# top.net
KiCad netlist of a schematic drawn in Altium Designer
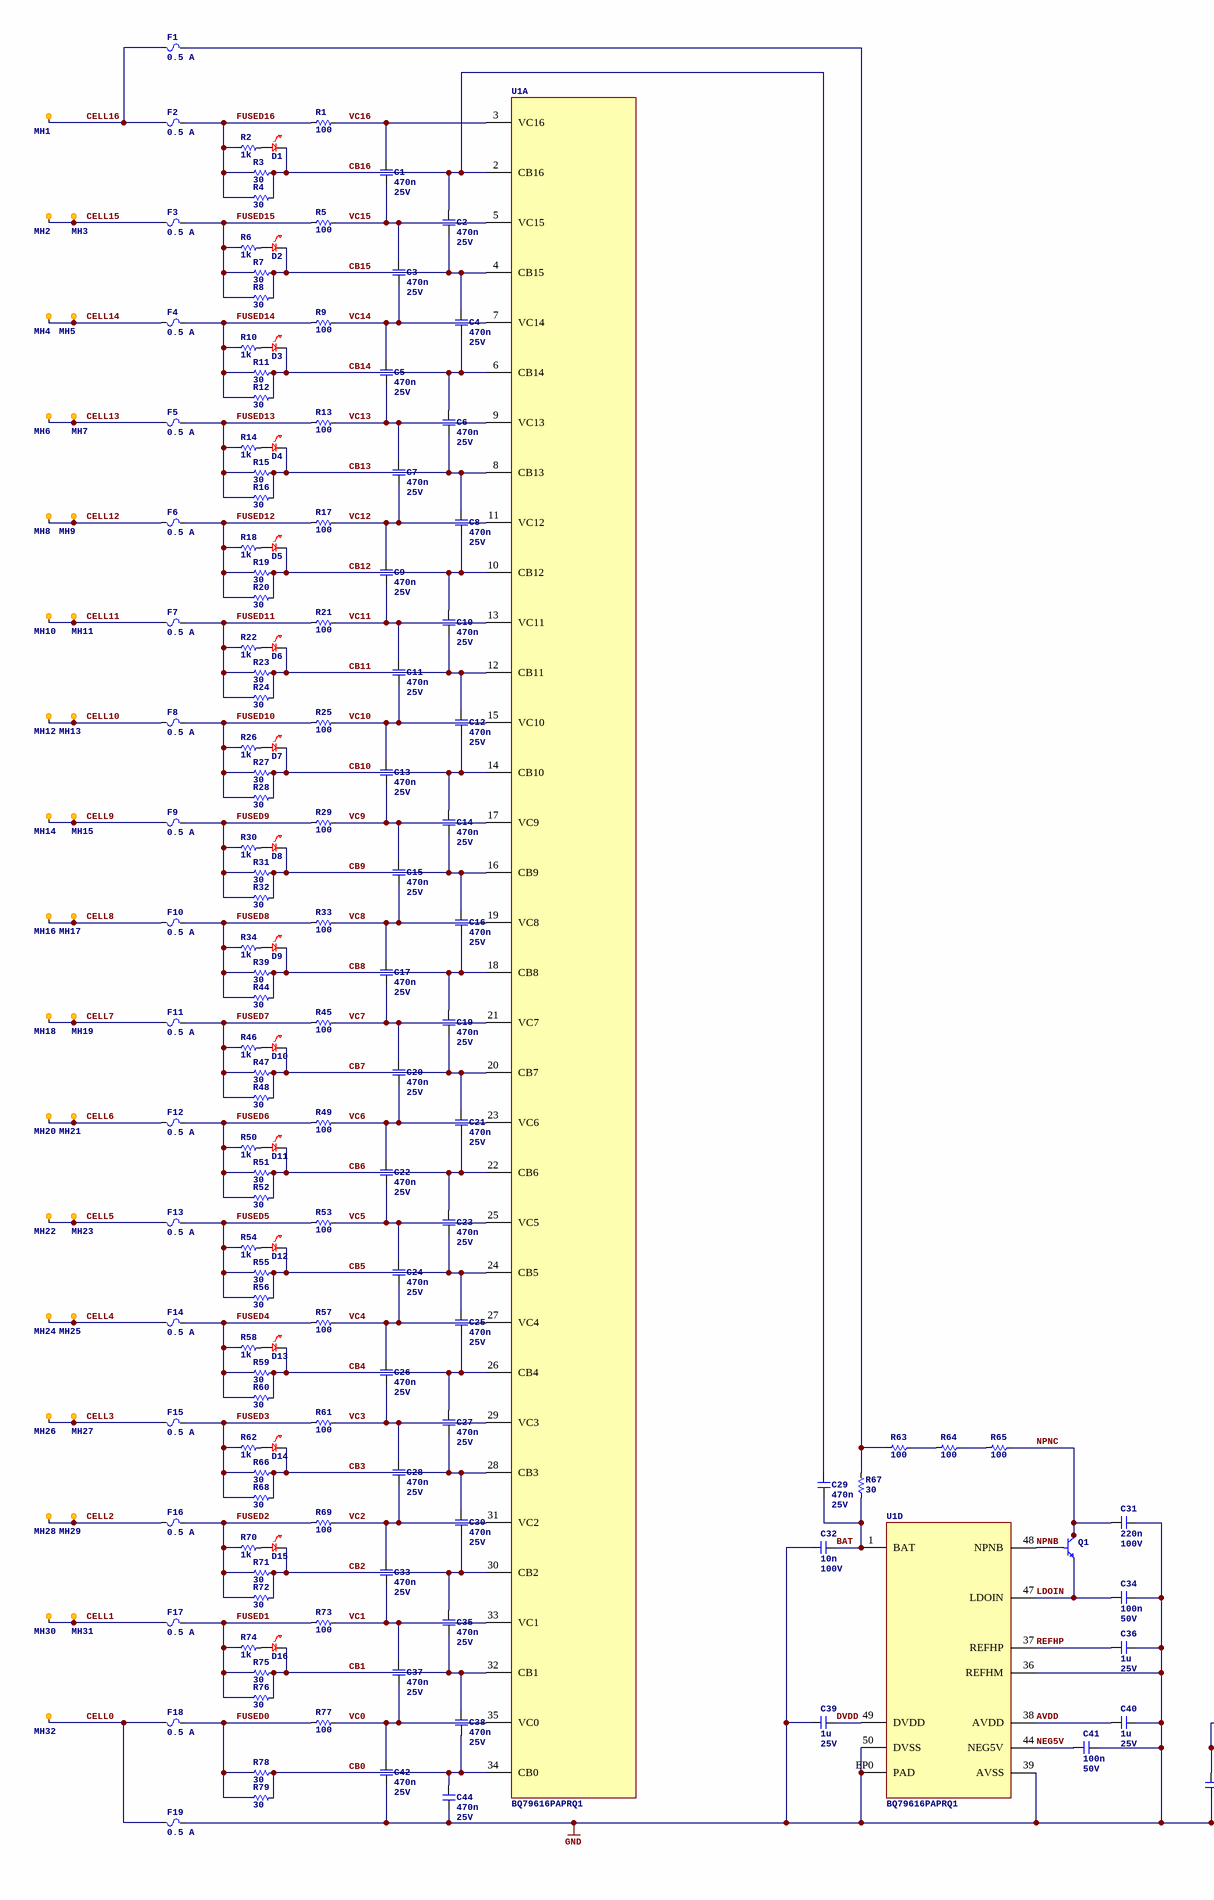
[diagram p0: top.SchDoc, left]
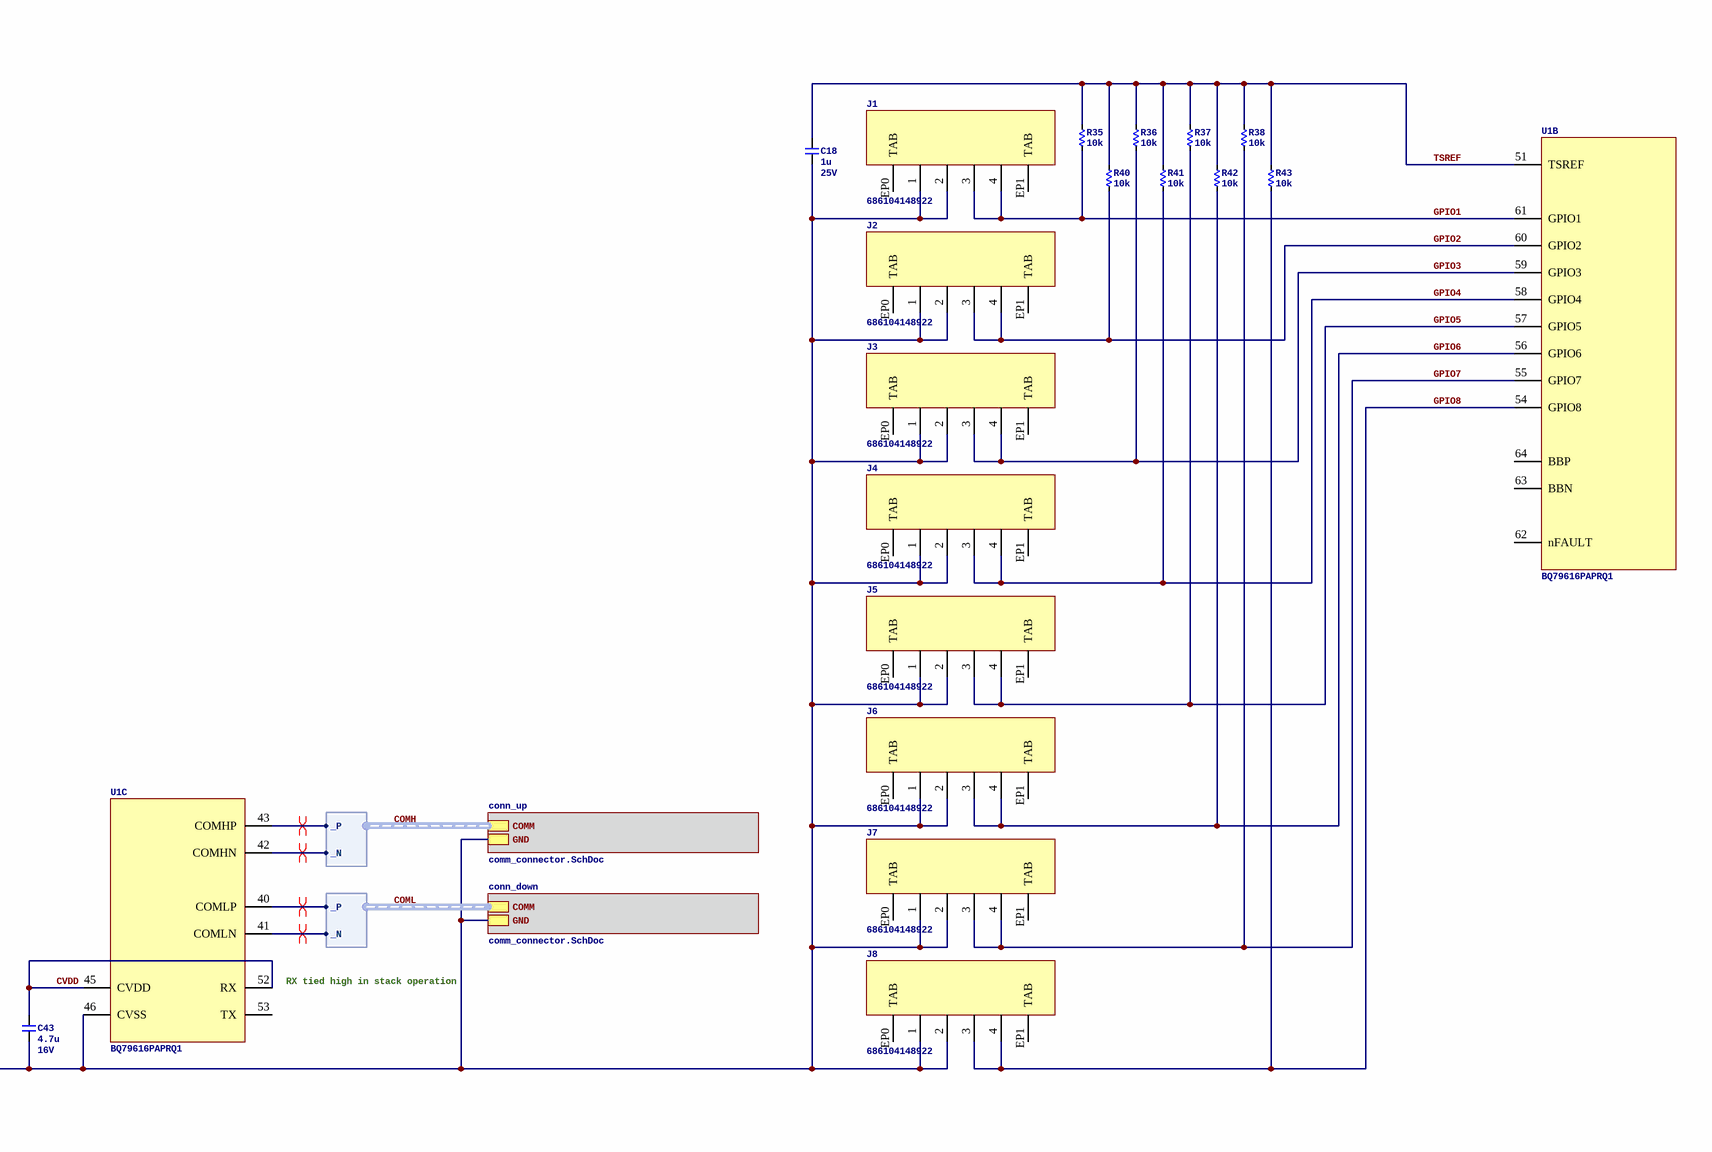
[diagram p1: top.SchDoc, right]

(export (version "E")
  (design (tool "Eeschema 10.0.6"))
  (components
    (comp (ref "C1")
      (value "CL10B474KA8NNNC")
      (footprint "C0603")
      (fields
        (field (name "CAPACITANCE") "470n")
        (field (name "MANUFACTURER") "Samsung Electro-Mechanics")
        (field (name "VOLTAGE RATING") "25V")
      )
      (libsource (lib "database") (part "__template_cap"))
    )
    (comp (ref "C2")
      (value "CL10B474KA8NNNC")
      (footprint "C0603")
      (fields
        (field (name "CAPACITANCE") "470n")
        (field (name "MANUFACTURER") "Samsung Electro-Mechanics")
        (field (name "VOLTAGE RATING") "25V")
      )
      (libsource (lib "database") (part "__template_cap"))
    )
    (comp (ref "C3")
      (value "CL10B474KA8NNNC")
      (footprint "C0603")
      (fields
        (field (name "CAPACITANCE") "470n")
        (field (name "MANUFACTURER") "Samsung Electro-Mechanics")
        (field (name "VOLTAGE RATING") "25V")
      )
      (libsource (lib "database") (part "__template_cap"))
    )
    (comp (ref "C4")
      (value "CL10B474KA8NNNC")
      (footprint "C0603")
      (fields
        (field (name "CAPACITANCE") "470n")
        (field (name "MANUFACTURER") "Samsung Electro-Mechanics")
        (field (name "VOLTAGE RATING") "25V")
      )
      (libsource (lib "database") (part "__template_cap"))
    )
    (comp (ref "C5")
      (value "CL10B474KA8NNNC")
      (footprint "C0603")
      (fields
        (field (name "CAPACITANCE") "470n")
        (field (name "MANUFACTURER") "Samsung Electro-Mechanics")
        (field (name "VOLTAGE RATING") "25V")
      )
      (libsource (lib "database") (part "__template_cap"))
    )
    (comp (ref "C6")
      (value "CL10B474KA8NNNC")
      (footprint "C0603")
      (fields
        (field (name "CAPACITANCE") "470n")
        (field (name "MANUFACTURER") "Samsung Electro-Mechanics")
        (field (name "VOLTAGE RATING") "25V")
      )
      (libsource (lib "database") (part "__template_cap"))
    )
    (comp (ref "C7")
      (value "CL10B474KA8NNNC")
      (footprint "C0603")
      (fields
        (field (name "CAPACITANCE") "470n")
        (field (name "MANUFACTURER") "Samsung Electro-Mechanics")
        (field (name "VOLTAGE RATING") "25V")
      )
      (libsource (lib "database") (part "__template_cap"))
    )
    (comp (ref "C8")
      (value "CL10B474KA8NNNC")
      (footprint "C0603")
      (fields
        (field (name "CAPACITANCE") "470n")
        (field (name "MANUFACTURER") "Samsung Electro-Mechanics")
        (field (name "VOLTAGE RATING") "25V")
      )
      (libsource (lib "database") (part "__template_cap"))
    )
    (comp (ref "C9")
      (value "CL10B474KA8NNNC")
      (footprint "C0603")
      (fields
        (field (name "CAPACITANCE") "470n")
        (field (name "MANUFACTURER") "Samsung Electro-Mechanics")
        (field (name "VOLTAGE RATING") "25V")
      )
      (libsource (lib "database") (part "__template_cap"))
    )
    (comp (ref "C10")
      (value "CL10B474KA8NNNC")
      (footprint "C0603")
      (fields
        (field (name "CAPACITANCE") "470n")
        (field (name "MANUFACTURER") "Samsung Electro-Mechanics")
        (field (name "VOLTAGE RATING") "25V")
      )
      (libsource (lib "database") (part "__template_cap"))
    )
    (comp (ref "C11")
      (value "CL10B474KA8NNNC")
      (footprint "C0603")
      (fields
        (field (name "CAPACITANCE") "470n")
        (field (name "MANUFACTURER") "Samsung Electro-Mechanics")
        (field (name "VOLTAGE RATING") "25V")
      )
      (libsource (lib "database") (part "__template_cap"))
    )
    (comp (ref "C12")
      (value "CL10B474KA8NNNC")
      (footprint "C0603")
      (fields
        (field (name "CAPACITANCE") "470n")
        (field (name "MANUFACTURER") "Samsung Electro-Mechanics")
        (field (name "VOLTAGE RATING") "25V")
      )
      (libsource (lib "database") (part "__template_cap"))
    )
    (comp (ref "C13")
      (value "CL10B474KA8NNNC")
      (footprint "C0603")
      (fields
        (field (name "CAPACITANCE") "470n")
        (field (name "MANUFACTURER") "Samsung Electro-Mechanics")
        (field (name "VOLTAGE RATING") "25V")
      )
      (libsource (lib "database") (part "__template_cap"))
    )
    (comp (ref "C14")
      (value "CL10B474KA8NNNC")
      (footprint "C0603")
      (fields
        (field (name "CAPACITANCE") "470n")
        (field (name "MANUFACTURER") "Samsung Electro-Mechanics")
        (field (name "VOLTAGE RATING") "25V")
      )
      (libsource (lib "database") (part "__template_cap"))
    )
    (comp (ref "C15")
      (value "CL10B474KA8NNNC")
      (footprint "C0603")
      (fields
        (field (name "CAPACITANCE") "470n")
        (field (name "MANUFACTURER") "Samsung Electro-Mechanics")
        (field (name "VOLTAGE RATING") "25V")
      )
      (libsource (lib "database") (part "__template_cap"))
    )
    (comp (ref "C16")
      (value "CL10B474KA8NNNC")
      (footprint "C0603")
      (fields
        (field (name "CAPACITANCE") "470n")
        (field (name "MANUFACTURER") "Samsung Electro-Mechanics")
        (field (name "VOLTAGE RATING") "25V")
      )
      (libsource (lib "database") (part "__template_cap"))
    )
    (comp (ref "C17")
      (value "CL10B474KA8NNNC")
      (footprint "C0603")
      (fields
        (field (name "CAPACITANCE") "470n")
        (field (name "MANUFACTURER") "Samsung Electro-Mechanics")
        (field (name "VOLTAGE RATING") "25V")
      )
      (libsource (lib "database") (part "__template_cap"))
    )
    (comp (ref "C18")
      (value "CL10B105KA8NNNC")
      (footprint "C0603")
      (fields
        (field (name "CAPACITANCE") "1u")
        (field (name "MANUFACTURER") "Samsung Electro-Mechanics")
        (field (name "VOLTAGE RATING") "25V")
      )
      (libsource (lib "database") (part "__template_cap"))
    )
    (comp (ref "C19")
      (value "CL10B474KA8NNNC")
      (footprint "C0603")
      (fields
        (field (name "CAPACITANCE") "470n")
        (field (name "MANUFACTURER") "Samsung Electro-Mechanics")
        (field (name "VOLTAGE RATING") "25V")
      )
      (libsource (lib "database") (part "__template_cap"))
    )
    (comp (ref "C20")
      (value "CL10B474KA8NNNC")
      (footprint "C0603")
      (fields
        (field (name "CAPACITANCE") "470n")
        (field (name "MANUFACTURER") "Samsung Electro-Mechanics")
        (field (name "VOLTAGE RATING") "25V")
      )
      (libsource (lib "database") (part "__template_cap"))
    )
    (comp (ref "C21")
      (value "CL10B474KA8NNNC")
      (footprint "C0603")
      (fields
        (field (name "CAPACITANCE") "470n")
        (field (name "MANUFACTURER") "Samsung Electro-Mechanics")
        (field (name "VOLTAGE RATING") "25V")
      )
      (libsource (lib "database") (part "__template_cap"))
    )
    (comp (ref "C22")
      (value "CL10B474KA8NNNC")
      (footprint "C0603")
      (fields
        (field (name "CAPACITANCE") "470n")
        (field (name "MANUFACTURER") "Samsung Electro-Mechanics")
        (field (name "VOLTAGE RATING") "25V")
      )
      (libsource (lib "database") (part "__template_cap"))
    )
    (comp (ref "C23")
      (value "CL10B474KA8NNNC")
      (footprint "C0603")
      (fields
        (field (name "CAPACITANCE") "470n")
        (field (name "MANUFACTURER") "Samsung Electro-Mechanics")
        (field (name "VOLTAGE RATING") "25V")
      )
      (libsource (lib "database") (part "__template_cap"))
    )
    (comp (ref "C24")
      (value "CL10B474KA8NNNC")
      (footprint "C0603")
      (fields
        (field (name "CAPACITANCE") "470n")
        (field (name "MANUFACTURER") "Samsung Electro-Mechanics")
        (field (name "VOLTAGE RATING") "25V")
      )
      (libsource (lib "database") (part "__template_cap"))
    )
    (comp (ref "C25")
      (value "CL10B474KA8NNNC")
      (footprint "C0603")
      (fields
        (field (name "CAPACITANCE") "470n")
        (field (name "MANUFACTURER") "Samsung Electro-Mechanics")
        (field (name "VOLTAGE RATING") "25V")
      )
      (libsource (lib "database") (part "__template_cap"))
    )
    (comp (ref "C26")
      (value "CL10B474KA8NNNC")
      (footprint "C0603")
      (fields
        (field (name "CAPACITANCE") "470n")
        (field (name "MANUFACTURER") "Samsung Electro-Mechanics")
        (field (name "VOLTAGE RATING") "25V")
      )
      (libsource (lib "database") (part "__template_cap"))
    )
    (comp (ref "C27")
      (value "CL10B474KA8NNNC")
      (footprint "C0603")
      (fields
        (field (name "CAPACITANCE") "470n")
        (field (name "MANUFACTURER") "Samsung Electro-Mechanics")
        (field (name "VOLTAGE RATING") "25V")
      )
      (libsource (lib "database") (part "__template_cap"))
    )
    (comp (ref "C28")
      (value "CL10B474KA8NNNC")
      (footprint "C0603")
      (fields
        (field (name "CAPACITANCE") "470n")
        (field (name "MANUFACTURER") "Samsung Electro-Mechanics")
        (field (name "VOLTAGE RATING") "25V")
      )
      (libsource (lib "database") (part "__template_cap"))
    )
    (comp (ref "C29")
      (value "CL10B474KA8NNNC")
      (footprint "C0603")
      (fields
        (field (name "CAPACITANCE") "470n")
        (field (name "MANUFACTURER") "Samsung Electro-Mechanics")
        (field (name "VOLTAGE RATING") "25V")
      )
      (libsource (lib "database") (part "__template_cap"))
    )
    (comp (ref "C30")
      (value "CL10B474KA8NNNC")
      (footprint "C0603")
      (fields
        (field (name "CAPACITANCE") "470n")
        (field (name "MANUFACTURER") "Samsung Electro-Mechanics")
        (field (name "VOLTAGE RATING") "25V")
      )
      (libsource (lib "database") (part "__template_cap"))
    )
    (comp (ref "C31")
      (value "TCC1206X7R224K101FT")
      (footprint "C1206")
      (fields
        (field (name "CAPACITANCE") "220n")
        (field (name "MANUFACTURER") "CCTC")
        (field (name "VOLTAGE RATING") "100V")
      )
      (libsource (lib "database") (part "__template_cap"))
    )
    (comp (ref "C32")
      (value "CC0402KRX7R0BB103")
      (footprint "C0402")
      (fields
        (field (name "CAPACITANCE") "10n")
        (field (name "MANUFACTURER") "YAGEO")
        (field (name "VOLTAGE RATING") "100V")
      )
      (libsource (lib "database") (part "__template_cap"))
    )
    (comp (ref "C33")
      (value "CL10B474KA8NNNC")
      (footprint "C0603")
      (fields
        (field (name "CAPACITANCE") "470n")
        (field (name "MANUFACTURER") "Samsung Electro-Mechanics")
        (field (name "VOLTAGE RATING") "25V")
      )
      (libsource (lib "database") (part "__template_cap"))
    )
    (comp (ref "C34")
      (value "CL05B104KB54PNC")
      (footprint "C0402")
      (fields
        (field (name "CAPACITANCE") "100n")
        (field (name "MANUFACTURER") "Samsung Electro-Mechanics")
        (field (name "VOLTAGE RATING") "50V")
      )
      (libsource (lib "database") (part "__template_cap"))
    )
    (comp (ref "C35")
      (value "CL10B474KA8NNNC")
      (footprint "C0603")
      (fields
        (field (name "CAPACITANCE") "470n")
        (field (name "MANUFACTURER") "Samsung Electro-Mechanics")
        (field (name "VOLTAGE RATING") "25V")
      )
      (libsource (lib "database") (part "__template_cap"))
    )
    (comp (ref "C36")
      (value "CL10B105KA8NNNC")
      (footprint "C0603")
      (fields
        (field (name "CAPACITANCE") "1u")
        (field (name "MANUFACTURER") "Samsung Electro-Mechanics")
        (field (name "VOLTAGE RATING") "25V")
      )
      (libsource (lib "database") (part "__template_cap"))
    )
    (comp (ref "C37")
      (value "CL10B474KA8NNNC")
      (footprint "C0603")
      (fields
        (field (name "CAPACITANCE") "470n")
        (field (name "MANUFACTURER") "Samsung Electro-Mechanics")
        (field (name "VOLTAGE RATING") "25V")
      )
      (libsource (lib "database") (part "__template_cap"))
    )
    (comp (ref "C38")
      (value "CL10B474KA8NNNC")
      (footprint "C0603")
      (fields
        (field (name "CAPACITANCE") "470n")
        (field (name "MANUFACTURER") "Samsung Electro-Mechanics")
        (field (name "VOLTAGE RATING") "25V")
      )
      (libsource (lib "database") (part "__template_cap"))
    )
    (comp (ref "C39")
      (value "CL10B105KA8NNNC")
      (footprint "C0603")
      (fields
        (field (name "CAPACITANCE") "1u")
        (field (name "MANUFACTURER") "Samsung Electro-Mechanics")
        (field (name "VOLTAGE RATING") "25V")
      )
      (libsource (lib "database") (part "__template_cap"))
    )
    (comp (ref "C40")
      (value "CL10B105KA8NNNC")
      (footprint "C0603")
      (fields
        (field (name "CAPACITANCE") "1u")
        (field (name "MANUFACTURER") "Samsung Electro-Mechanics")
        (field (name "VOLTAGE RATING") "25V")
      )
      (libsource (lib "database") (part "__template_cap"))
    )
    (comp (ref "C41")
      (value "CL05B104KB54PNC")
      (footprint "C0402")
      (fields
        (field (name "CAPACITANCE") "100n")
        (field (name "MANUFACTURER") "Samsung Electro-Mechanics")
        (field (name "VOLTAGE RATING") "50V")
      )
      (libsource (lib "database") (part "__template_cap"))
    )
    (comp (ref "C42")
      (value "CL10B474KA8NNNC")
      (footprint "C0603")
      (fields
        (field (name "CAPACITANCE") "470n")
        (field (name "MANUFACTURER") "Samsung Electro-Mechanics")
        (field (name "VOLTAGE RATING") "25V")
      )
      (libsource (lib "database") (part "__template_cap"))
    )
    (comp (ref "C43")
      (value "CL21B475KOFNNNE")
      (footprint "C0805")
      (fields
        (field (name "CAPACITANCE") "4.7u")
        (field (name "MANUFACTURER") "Samsung Electro-Mechanics")
        (field (name "VOLTAGE RATING") "16V")
      )
      (libsource (lib "database") (part "__template_cap"))
    )
    (comp (ref "C44")
      (value "CL10B474KA8NNNC")
      (footprint "C0603")
      (fields
        (field (name "CAPACITANCE") "470n")
        (field (name "MANUFACTURER") "Samsung Electro-Mechanics")
        (field (name "VOLTAGE RATING") "25V")
      )
      (libsource (lib "database") (part "__template_cap"))
    )
    (comp (ref "D1")
      (value "LTST-C190KRKT")
      (footprint "LED_0603P_RED")
      (description "LED SUPER RED CLEAR 0603 SMD")
      (fields (field (name "MANUFACTURER") "Lite-On Inc"))
      (libsource (lib "SSCP") (part "LED_0603_RED_LTST-C190KRKT"))
    )
    (comp (ref "D2")
      (value "LTST-C190KRKT")
      (footprint "LED_0603P_RED")
      (description "LED SUPER RED CLEAR 0603 SMD")
      (fields (field (name "MANUFACTURER") "Lite-On Inc"))
      (libsource (lib "SSCP") (part "LED_0603_RED_LTST-C190KRKT"))
    )
    (comp (ref "D3")
      (value "LTST-C190KRKT")
      (footprint "LED_0603P_RED")
      (description "LED SUPER RED CLEAR 0603 SMD")
      (fields (field (name "MANUFACTURER") "Lite-On Inc"))
      (libsource (lib "SSCP") (part "LED_0603_RED_LTST-C190KRKT"))
    )
    (comp (ref "D4")
      (value "LTST-C190KRKT")
      (footprint "LED_0603P_RED")
      (description "LED SUPER RED CLEAR 0603 SMD")
      (fields (field (name "MANUFACTURER") "Lite-On Inc"))
      (libsource (lib "SSCP") (part "LED_0603_RED_LTST-C190KRKT"))
    )
    (comp (ref "D5")
      (value "LTST-C190KRKT")
      (footprint "LED_0603P_RED")
      (description "LED SUPER RED CLEAR 0603 SMD")
      (fields (field (name "MANUFACTURER") "Lite-On Inc"))
      (libsource (lib "SSCP") (part "LED_0603_RED_LTST-C190KRKT"))
    )
    (comp (ref "D6")
      (value "LTST-C190KRKT")
      (footprint "LED_0603P_RED")
      (description "LED SUPER RED CLEAR 0603 SMD")
      (fields (field (name "MANUFACTURER") "Lite-On Inc"))
      (libsource (lib "SSCP") (part "LED_0603_RED_LTST-C190KRKT"))
    )
    (comp (ref "D7")
      (value "LTST-C190KRKT")
      (footprint "LED_0603P_RED")
      (description "LED SUPER RED CLEAR 0603 SMD")
      (fields (field (name "MANUFACTURER") "Lite-On Inc"))
      (libsource (lib "SSCP") (part "LED_0603_RED_LTST-C190KRKT"))
    )
    (comp (ref "D8")
      (value "LTST-C190KRKT")
      (footprint "LED_0603P_RED")
      (description "LED SUPER RED CLEAR 0603 SMD")
      (fields (field (name "MANUFACTURER") "Lite-On Inc"))
      (libsource (lib "SSCP") (part "LED_0603_RED_LTST-C190KRKT"))
    )
    (comp (ref "D9")
      (value "LTST-C190KRKT")
      (footprint "LED_0603P_RED")
      (description "LED SUPER RED CLEAR 0603 SMD")
      (fields (field (name "MANUFACTURER") "Lite-On Inc"))
      (libsource (lib "SSCP") (part "LED_0603_RED_LTST-C190KRKT"))
    )
    (comp (ref "D10")
      (value "LTST-C190KRKT")
      (footprint "LED_0603P_RED")
      (description "LED SUPER RED CLEAR 0603 SMD")
      (fields (field (name "MANUFACTURER") "Lite-On Inc"))
      (libsource (lib "SSCP") (part "LED_0603_RED_LTST-C190KRKT"))
    )
    (comp (ref "D11")
      (value "LTST-C190KRKT")
      (footprint "LED_0603P_RED")
      (description "LED SUPER RED CLEAR 0603 SMD")
      (fields (field (name "MANUFACTURER") "Lite-On Inc"))
      (libsource (lib "SSCP") (part "LED_0603_RED_LTST-C190KRKT"))
    )
    (comp (ref "D12")
      (value "LTST-C190KRKT")
      (footprint "LED_0603P_RED")
      (description "LED SUPER RED CLEAR 0603 SMD")
      (fields (field (name "MANUFACTURER") "Lite-On Inc"))
      (libsource (lib "SSCP") (part "LED_0603_RED_LTST-C190KRKT"))
    )
    (comp (ref "D13")
      (value "LTST-C190KRKT")
      (footprint "LED_0603P_RED")
      (description "LED SUPER RED CLEAR 0603 SMD")
      (fields (field (name "MANUFACTURER") "Lite-On Inc"))
      (libsource (lib "SSCP") (part "LED_0603_RED_LTST-C190KRKT"))
    )
    (comp (ref "D14")
      (value "LTST-C190KRKT")
      (footprint "LED_0603P_RED")
      (description "LED SUPER RED CLEAR 0603 SMD")
      (fields (field (name "MANUFACTURER") "Lite-On Inc"))
      (libsource (lib "SSCP") (part "LED_0603_RED_LTST-C190KRKT"))
    )
    (comp (ref "D15")
      (value "LTST-C190KRKT")
      (footprint "LED_0603P_RED")
      (description "LED SUPER RED CLEAR 0603 SMD")
      (fields (field (name "MANUFACTURER") "Lite-On Inc"))
      (libsource (lib "SSCP") (part "LED_0603_RED_LTST-C190KRKT"))
    )
    (comp (ref "D16")
      (value "LTST-C190KRKT")
      (footprint "LED_0603P_RED")
      (description "LED SUPER RED CLEAR 0603 SMD")
      (fields (field (name "MANUFACTURER") "Lite-On Inc"))
      (libsource (lib "SSCP") (part "LED_0603_RED_LTST-C190KRKT"))
    )
    (comp (ref "F1")
      (value "JFC2410-0500TS")
      (footprint "JDTFUSE_JFC2410")
      (description "FUSE 0.5A 250V SMD")
      (fields (field (name "MANUFACTURER") "Shenzhen JDTfuse") (field (name "CURRENT") "0.5 A"))
      (libsource (lib "SSCP") (part "FUSE_SLOW_0.5A_JFC2410-0500TS"))
    )
    (comp (ref "F2")
      (value "JFC2410-0500TS")
      (footprint "JDTFUSE_JFC2410")
      (description "FUSE 0.5A 250V SMD")
      (fields (field (name "MANUFACTURER") "Shenzhen JDTfuse") (field (name "CURRENT") "0.5 A"))
      (libsource (lib "SSCP") (part "FUSE_SLOW_0.5A_JFC2410-0500TS"))
    )
    (comp (ref "F3")
      (value "JFC2410-0500TS")
      (footprint "JDTFUSE_JFC2410")
      (description "FUSE 0.5A 250V SMD")
      (fields (field (name "MANUFACTURER") "Shenzhen JDTfuse") (field (name "CURRENT") "0.5 A"))
      (libsource (lib "SSCP") (part "FUSE_SLOW_0.5A_JFC2410-0500TS"))
    )
    (comp (ref "F4")
      (value "JFC2410-0500TS")
      (footprint "JDTFUSE_JFC2410")
      (description "FUSE 0.5A 250V SMD")
      (fields (field (name "MANUFACTURER") "Shenzhen JDTfuse") (field (name "CURRENT") "0.5 A"))
      (libsource (lib "SSCP") (part "FUSE_SLOW_0.5A_JFC2410-0500TS"))
    )
    (comp (ref "F5")
      (value "JFC2410-0500TS")
      (footprint "JDTFUSE_JFC2410")
      (description "FUSE 0.5A 250V SMD")
      (fields (field (name "MANUFACTURER") "Shenzhen JDTfuse") (field (name "CURRENT") "0.5 A"))
      (libsource (lib "SSCP") (part "FUSE_SLOW_0.5A_JFC2410-0500TS"))
    )
    (comp (ref "F6")
      (value "JFC2410-0500TS")
      (footprint "JDTFUSE_JFC2410")
      (description "FUSE 0.5A 250V SMD")
      (fields (field (name "MANUFACTURER") "Shenzhen JDTfuse") (field (name "CURRENT") "0.5 A"))
      (libsource (lib "SSCP") (part "FUSE_SLOW_0.5A_JFC2410-0500TS"))
    )
    (comp (ref "F7")
      (value "JFC2410-0500TS")
      (footprint "JDTFUSE_JFC2410")
      (description "FUSE 0.5A 250V SMD")
      (fields (field (name "MANUFACTURER") "Shenzhen JDTfuse") (field (name "CURRENT") "0.5 A"))
      (libsource (lib "SSCP") (part "FUSE_SLOW_0.5A_JFC2410-0500TS"))
    )
    (comp (ref "F8")
      (value "JFC2410-0500TS")
      (footprint "JDTFUSE_JFC2410")
      (description "FUSE 0.5A 250V SMD")
      (fields (field (name "MANUFACTURER") "Shenzhen JDTfuse") (field (name "CURRENT") "0.5 A"))
      (libsource (lib "SSCP") (part "FUSE_SLOW_0.5A_JFC2410-0500TS"))
    )
    (comp (ref "F9")
      (value "JFC2410-0500TS")
      (footprint "JDTFUSE_JFC2410")
      (description "FUSE 0.5A 250V SMD")
      (fields (field (name "MANUFACTURER") "Shenzhen JDTfuse") (field (name "CURRENT") "0.5 A"))
      (libsource (lib "SSCP") (part "FUSE_SLOW_0.5A_JFC2410-0500TS"))
    )
    (comp (ref "F10")
      (value "JFC2410-0500TS")
      (footprint "JDTFUSE_JFC2410")
      (description "FUSE 0.5A 250V SMD")
      (fields (field (name "MANUFACTURER") "Shenzhen JDTfuse") (field (name "CURRENT") "0.5 A"))
      (libsource (lib "SSCP") (part "FUSE_SLOW_0.5A_JFC2410-0500TS"))
    )
    (comp (ref "F11")
      (value "JFC2410-0500TS")
      (footprint "JDTFUSE_JFC2410")
      (description "FUSE 0.5A 250V SMD")
      (fields (field (name "MANUFACTURER") "Shenzhen JDTfuse") (field (name "CURRENT") "0.5 A"))
      (libsource (lib "SSCP") (part "FUSE_SLOW_0.5A_JFC2410-0500TS"))
    )
    (comp (ref "F12")
      (value "JFC2410-0500TS")
      (footprint "JDTFUSE_JFC2410")
      (description "FUSE 0.5A 250V SMD")
      (fields (field (name "MANUFACTURER") "Shenzhen JDTfuse") (field (name "CURRENT") "0.5 A"))
      (libsource (lib "SSCP") (part "FUSE_SLOW_0.5A_JFC2410-0500TS"))
    )
    (comp (ref "F13")
      (value "JFC2410-0500TS")
      (footprint "JDTFUSE_JFC2410")
      (description "FUSE 0.5A 250V SMD")
      (fields (field (name "MANUFACTURER") "Shenzhen JDTfuse") (field (name "CURRENT") "0.5 A"))
      (libsource (lib "SSCP") (part "FUSE_SLOW_0.5A_JFC2410-0500TS"))
    )
    (comp (ref "F14")
      (value "JFC2410-0500TS")
      (footprint "JDTFUSE_JFC2410")
      (description "FUSE 0.5A 250V SMD")
      (fields (field (name "MANUFACTURER") "Shenzhen JDTfuse") (field (name "CURRENT") "0.5 A"))
      (libsource (lib "SSCP") (part "FUSE_SLOW_0.5A_JFC2410-0500TS"))
    )
    (comp (ref "F15")
      (value "JFC2410-0500TS")
      (footprint "JDTFUSE_JFC2410")
      (description "FUSE 0.5A 250V SMD")
      (fields (field (name "MANUFACTURER") "Shenzhen JDTfuse") (field (name "CURRENT") "0.5 A"))
      (libsource (lib "SSCP") (part "FUSE_SLOW_0.5A_JFC2410-0500TS"))
    )
    (comp (ref "F16")
      (value "JFC2410-0500TS")
      (footprint "JDTFUSE_JFC2410")
      (description "FUSE 0.5A 250V SMD")
      (fields (field (name "MANUFACTURER") "Shenzhen JDTfuse") (field (name "CURRENT") "0.5 A"))
      (libsource (lib "SSCP") (part "FUSE_SLOW_0.5A_JFC2410-0500TS"))
    )
    (comp (ref "F17")
      (value "JFC2410-0500TS")
      (footprint "JDTFUSE_JFC2410")
      (description "FUSE 0.5A 250V SMD")
      (fields (field (name "MANUFACTURER") "Shenzhen JDTfuse") (field (name "CURRENT") "0.5 A"))
      (libsource (lib "SSCP") (part "FUSE_SLOW_0.5A_JFC2410-0500TS"))
    )
    (comp (ref "F18")
      (value "JFC2410-0500TS")
      (footprint "JDTFUSE_JFC2410")
      (description "FUSE 0.5A 250V SMD")
      (fields (field (name "MANUFACTURER") "Shenzhen JDTfuse") (field (name "CURRENT") "0.5 A"))
      (libsource (lib "SSCP") (part "FUSE_SLOW_0.5A_JFC2410-0500TS"))
    )
    (comp (ref "F19")
      (value "JFC2410-0500TS")
      (footprint "JDTFUSE_JFC2410")
      (description "FUSE 0.5A 250V SMD")
      (fields (field (name "MANUFACTURER") "Shenzhen JDTfuse") (field (name "CURRENT") "0.5 A"))
      (libsource (lib "SSCP") (part "FUSE_SLOW_0.5A_JFC2410-0500TS"))
    )
    (comp (ref "J1")
      (value "686104148922")
      (footprint "WURTH_WR-FPC_1.00mm_686104148922")
      (description "WR-FPC 1mm SMT Horiz. Bot. Contact Hinge type")
      (fields (field (name "MANUFACTURER") "Wurth Elektronik"))
      (libsource (lib "SSCP") (part "CONN_WURTH_WR-FPC_4POS_1.00mm_686104148922"))
    )
    (comp (ref "J2")
      (value "686104148922")
      (footprint "WURTH_WR-FPC_1.00mm_686104148922")
      (description "WR-FPC 1mm SMT Horiz. Bot. Contact Hinge type")
      (fields (field (name "MANUFACTURER") "Wurth Elektronik"))
      (libsource (lib "SSCP") (part "CONN_WURTH_WR-FPC_4POS_1.00mm_686104148922"))
    )
    (comp (ref "J3")
      (value "686104148922")
      (footprint "WURTH_WR-FPC_1.00mm_686104148922")
      (description "WR-FPC 1mm SMT Horiz. Bot. Contact Hinge type")
      (fields (field (name "MANUFACTURER") "Wurth Elektronik"))
      (libsource (lib "SSCP") (part "CONN_WURTH_WR-FPC_4POS_1.00mm_686104148922"))
    )
    (comp (ref "J4")
      (value "686104148922")
      (footprint "WURTH_WR-FPC_1.00mm_686104148922")
      (description "WR-FPC 1mm SMT Horiz. Bot. Contact Hinge type")
      (fields (field (name "MANUFACTURER") "Wurth Elektronik"))
      (libsource (lib "SSCP") (part "CONN_WURTH_WR-FPC_4POS_1.00mm_686104148922"))
    )
    (comp (ref "J5")
      (value "686104148922")
      (footprint "WURTH_WR-FPC_1.00mm_686104148922")
      (description "WR-FPC 1mm SMT Horiz. Bot. Contact Hinge type")
      (fields (field (name "MANUFACTURER") "Wurth Elektronik"))
      (libsource (lib "SSCP") (part "CONN_WURTH_WR-FPC_4POS_1.00mm_686104148922"))
    )
    (comp (ref "J6")
      (value "686104148922")
      (footprint "WURTH_WR-FPC_1.00mm_686104148922")
      (description "WR-FPC 1mm SMT Horiz. Bot. Contact Hinge type")
      (fields (field (name "MANUFACTURER") "Wurth Elektronik"))
      (libsource (lib "SSCP") (part "CONN_WURTH_WR-FPC_4POS_1.00mm_686104148922"))
    )
    (comp (ref "J7")
      (value "686104148922")
      (footprint "WURTH_WR-FPC_1.00mm_686104148922")
      (description "WR-FPC 1mm SMT Horiz. Bot. Contact Hinge type")
      (fields (field (name "MANUFACTURER") "Wurth Elektronik"))
      (libsource (lib "SSCP") (part "CONN_WURTH_WR-FPC_4POS_1.00mm_686104148922"))
    )
    (comp (ref "J8")
      (value "686104148922")
      (footprint "WURTH_WR-FPC_1.00mm_686104148922")
      (description "WR-FPC 1mm SMT Horiz. Bot. Contact Hinge type")
      (fields (field (name "MANUFACTURER") "Wurth Elektronik"))
      (libsource (lib "SSCP") (part "CONN_WURTH_WR-FPC_4POS_1.00mm_686104148922"))
    )
    (comp (ref "MH1") (value "HOLE") (footprint "HOLE_M2") (libsource (lib "SSCP") (part "HOLE")))
    (comp (ref "MH2") (value "HOLE") (footprint "HOLE_M2") (libsource (lib "SSCP") (part "HOLE")))
    (comp (ref "MH3") (value "HOLE") (footprint "HOLE_M2") (libsource (lib "SSCP") (part "HOLE")))
    (comp (ref "MH4") (value "HOLE") (footprint "HOLE_M2") (libsource (lib "SSCP") (part "HOLE")))
    (comp (ref "MH5") (value "HOLE") (footprint "HOLE_M2") (libsource (lib "SSCP") (part "HOLE")))
    (comp (ref "MH6") (value "HOLE") (footprint "HOLE_M2") (libsource (lib "SSCP") (part "HOLE")))
    (comp (ref "MH7") (value "HOLE") (footprint "HOLE_M2") (libsource (lib "SSCP") (part "HOLE")))
    (comp (ref "MH8") (value "HOLE") (footprint "HOLE_M2") (libsource (lib "SSCP") (part "HOLE")))
    (comp (ref "MH9") (value "HOLE") (footprint "HOLE_M2") (libsource (lib "SSCP") (part "HOLE")))
    (comp (ref "MH10") (value "HOLE") (footprint "HOLE_M2") (libsource (lib "SSCP") (part "HOLE")))
    (comp (ref "MH11") (value "HOLE") (footprint "HOLE_M2") (libsource (lib "SSCP") (part "HOLE")))
    (comp (ref "MH12") (value "HOLE") (footprint "HOLE_M2") (libsource (lib "SSCP") (part "HOLE")))
    (comp (ref "MH13") (value "HOLE") (footprint "HOLE_M2") (libsource (lib "SSCP") (part "HOLE")))
    (comp (ref "MH14") (value "HOLE") (footprint "HOLE_M2") (libsource (lib "SSCP") (part "HOLE")))
    (comp (ref "MH15") (value "HOLE") (footprint "HOLE_M2") (libsource (lib "SSCP") (part "HOLE")))
    (comp (ref "MH16") (value "HOLE") (footprint "HOLE_M2") (libsource (lib "SSCP") (part "HOLE")))
    (comp (ref "MH17") (value "HOLE") (footprint "HOLE_M2") (libsource (lib "SSCP") (part "HOLE")))
    (comp (ref "MH18") (value "HOLE") (footprint "HOLE_M2") (libsource (lib "SSCP") (part "HOLE")))
    (comp (ref "MH19") (value "HOLE") (footprint "HOLE_M2") (libsource (lib "SSCP") (part "HOLE")))
    (comp (ref "MH20") (value "HOLE") (footprint "HOLE_M2") (libsource (lib "SSCP") (part "HOLE")))
    (comp (ref "MH21") (value "HOLE") (footprint "HOLE_M2") (libsource (lib "SSCP") (part "HOLE")))
    (comp (ref "MH22") (value "HOLE") (footprint "HOLE_M2") (libsource (lib "SSCP") (part "HOLE")))
    (comp (ref "MH23") (value "HOLE") (footprint "HOLE_M2") (libsource (lib "SSCP") (part "HOLE")))
    (comp (ref "MH24") (value "HOLE") (footprint "HOLE_M2") (libsource (lib "SSCP") (part "HOLE")))
    (comp (ref "MH25") (value "HOLE") (footprint "HOLE_M2") (libsource (lib "SSCP") (part "HOLE")))
    (comp (ref "MH26") (value "HOLE") (footprint "HOLE_M2") (libsource (lib "SSCP") (part "HOLE")))
    (comp (ref "MH27") (value "HOLE") (footprint "HOLE_M2") (libsource (lib "SSCP") (part "HOLE")))
    (comp (ref "MH28") (value "HOLE") (footprint "HOLE_M2") (libsource (lib "SSCP") (part "HOLE")))
    (comp (ref "MH29") (value "HOLE") (footprint "HOLE_M2") (libsource (lib "SSCP") (part "HOLE")))
    (comp (ref "MH30") (value "HOLE") (footprint "HOLE_M2") (libsource (lib "SSCP") (part "HOLE")))
    (comp (ref "MH31") (value "HOLE") (footprint "HOLE_M2") (libsource (lib "SSCP") (part "HOLE")))
    (comp (ref "MH32") (value "HOLE") (footprint "HOLE_M2") (libsource (lib "SSCP") (part "HOLE")))
    (comp (ref "Q1")
      (value "NSV1C201MZ4T1G")
      (footprint "4SOT223")
      (description "Small Signal Bipolar Transistor, 2A I(C), 100V V(BR)CEO, 1-Element, NPN, Silicon, TO-261AA")
      (fields (field (name "MANUFACTURER") "ON Semiconductor"))
      (libsource (lib "SSCP") (part "NPN_100V_NSV1C201MZ4T1G"))
    )
    (comp (ref "R1")
      (value "100")
      (footprint "R0402")
      (fields
        (field (name "MANUFACTURER PART NUMBER") "RC0402FR-07100RL")
        (field (name "MANUFACTURER") "YAGEO")
        (field (name "TOLERANCE") "1%")
      )
      (libsource (lib "database") (part "__template_resistor"))
    )
    (comp (ref "R2")
      (value "1k")
      (footprint "R0402")
      (fields
        (field (name "TOLERANCE") "1%")
        (field (name "MANUFACTURER PART NUMBER") "0402WGF1001TCE")
        (field (name "MANUFACTURER") "UNI-ROYAL(Uniroyal Elec)")
      )
      (libsource (lib "database") (part "__template_resistor"))
    )
    (comp (ref "R3")
      (value "30")
      (footprint "R2512")
      (fields
        (field (name "MANUFACTURER PART NUMBER") "RC2512FK-0730RL")
        (field (name "MANUFACTURER") "YAGEO")
        (field (name "TOLERANCE") "1%")
      )
      (libsource (lib "database") (part "__template_resistor"))
    )
    (comp (ref "R4")
      (value "30")
      (footprint "R2512")
      (fields
        (field (name "MANUFACTURER PART NUMBER") "RC2512FK-0730RL")
        (field (name "MANUFACTURER") "YAGEO")
        (field (name "TOLERANCE") "1%")
      )
      (libsource (lib "database") (part "__template_resistor"))
    )
    (comp (ref "R5")
      (value "100")
      (footprint "R0402")
      (fields
        (field (name "MANUFACTURER PART NUMBER") "RC0402FR-07100RL")
        (field (name "MANUFACTURER") "YAGEO")
        (field (name "TOLERANCE") "1%")
      )
      (libsource (lib "database") (part "__template_resistor"))
    )
    (comp (ref "R6")
      (value "1k")
      (footprint "R0402")
      (fields
        (field (name "TOLERANCE") "1%")
        (field (name "MANUFACTURER PART NUMBER") "0402WGF1001TCE")
        (field (name "MANUFACTURER") "UNI-ROYAL(Uniroyal Elec)")
      )
      (libsource (lib "database") (part "__template_resistor"))
    )
    (comp (ref "R7")
      (value "30")
      (footprint "R2512")
      (fields
        (field (name "MANUFACTURER PART NUMBER") "RC2512FK-0730RL")
        (field (name "MANUFACTURER") "YAGEO")
        (field (name "TOLERANCE") "1%")
      )
      (libsource (lib "database") (part "__template_resistor"))
    )
    (comp (ref "R8")
      (value "30")
      (footprint "R2512")
      (fields
        (field (name "MANUFACTURER PART NUMBER") "RC2512FK-0730RL")
        (field (name "MANUFACTURER") "YAGEO")
        (field (name "TOLERANCE") "1%")
      )
      (libsource (lib "database") (part "__template_resistor"))
    )
    (comp (ref "R9")
      (value "100")
      (footprint "R0402")
      (fields
        (field (name "MANUFACTURER PART NUMBER") "RC0402FR-07100RL")
        (field (name "MANUFACTURER") "YAGEO")
        (field (name "TOLERANCE") "1%")
      )
      (libsource (lib "database") (part "__template_resistor"))
    )
    (comp (ref "R10")
      (value "1k")
      (footprint "R0402")
      (fields
        (field (name "TOLERANCE") "1%")
        (field (name "MANUFACTURER PART NUMBER") "0402WGF1001TCE")
        (field (name "MANUFACTURER") "UNI-ROYAL(Uniroyal Elec)")
      )
      (libsource (lib "database") (part "__template_resistor"))
    )
    (comp (ref "R11")
      (value "30")
      (footprint "R2512")
      (fields
        (field (name "MANUFACTURER PART NUMBER") "RC2512FK-0730RL")
        (field (name "MANUFACTURER") "YAGEO")
        (field (name "TOLERANCE") "1%")
      )
      (libsource (lib "database") (part "__template_resistor"))
    )
    (comp (ref "R12")
      (value "30")
      (footprint "R2512")
      (fields
        (field (name "MANUFACTURER PART NUMBER") "RC2512FK-0730RL")
        (field (name "MANUFACTURER") "YAGEO")
        (field (name "TOLERANCE") "1%")
      )
      (libsource (lib "database") (part "__template_resistor"))
    )
    (comp (ref "R13")
      (value "100")
      (footprint "R0402")
      (fields
        (field (name "MANUFACTURER PART NUMBER") "RC0402FR-07100RL")
        (field (name "MANUFACTURER") "YAGEO")
        (field (name "TOLERANCE") "1%")
      )
      (libsource (lib "database") (part "__template_resistor"))
    )
    (comp (ref "R14")
      (value "1k")
      (footprint "R0402")
      (fields
        (field (name "TOLERANCE") "1%")
        (field (name "MANUFACTURER PART NUMBER") "0402WGF1001TCE")
        (field (name "MANUFACTURER") "UNI-ROYAL(Uniroyal Elec)")
      )
      (libsource (lib "database") (part "__template_resistor"))
    )
    (comp (ref "R15")
      (value "30")
      (footprint "R2512")
      (fields
        (field (name "MANUFACTURER PART NUMBER") "RC2512FK-0730RL")
        (field (name "MANUFACTURER") "YAGEO")
        (field (name "TOLERANCE") "1%")
      )
      (libsource (lib "database") (part "__template_resistor"))
    )
    (comp (ref "R16")
      (value "30")
      (footprint "R2512")
      (fields
        (field (name "MANUFACTURER PART NUMBER") "RC2512FK-0730RL")
        (field (name "MANUFACTURER") "YAGEO")
        (field (name "TOLERANCE") "1%")
      )
      (libsource (lib "database") (part "__template_resistor"))
    )
    (comp (ref "R17")
      (value "100")
      (footprint "R0402")
      (fields
        (field (name "MANUFACTURER PART NUMBER") "RC0402FR-07100RL")
        (field (name "MANUFACTURER") "YAGEO")
        (field (name "TOLERANCE") "1%")
      )
      (libsource (lib "database") (part "__template_resistor"))
    )
    (comp (ref "R18")
      (value "1k")
      (footprint "R0402")
      (fields
        (field (name "TOLERANCE") "1%")
        (field (name "MANUFACTURER PART NUMBER") "0402WGF1001TCE")
        (field (name "MANUFACTURER") "UNI-ROYAL(Uniroyal Elec)")
      )
      (libsource (lib "database") (part "__template_resistor"))
    )
    (comp (ref "R19")
      (value "30")
      (footprint "R2512")
      (fields
        (field (name "MANUFACTURER PART NUMBER") "RC2512FK-0730RL")
        (field (name "MANUFACTURER") "YAGEO")
        (field (name "TOLERANCE") "1%")
      )
      (libsource (lib "database") (part "__template_resistor"))
    )
    (comp (ref "R20")
      (value "30")
      (footprint "R2512")
      (fields
        (field (name "MANUFACTURER PART NUMBER") "RC2512FK-0730RL")
        (field (name "MANUFACTURER") "YAGEO")
        (field (name "TOLERANCE") "1%")
      )
      (libsource (lib "database") (part "__template_resistor"))
    )
    (comp (ref "R21")
      (value "100")
      (footprint "R0402")
      (fields
        (field (name "MANUFACTURER PART NUMBER") "RC0402FR-07100RL")
        (field (name "MANUFACTURER") "YAGEO")
        (field (name "TOLERANCE") "1%")
      )
      (libsource (lib "database") (part "__template_resistor"))
    )
    (comp (ref "R22")
      (value "1k")
      (footprint "R0402")
      (fields
        (field (name "TOLERANCE") "1%")
        (field (name "MANUFACTURER PART NUMBER") "0402WGF1001TCE")
        (field (name "MANUFACTURER") "UNI-ROYAL(Uniroyal Elec)")
      )
      (libsource (lib "database") (part "__template_resistor"))
    )
    (comp (ref "R23")
      (value "30")
      (footprint "R2512")
      (fields
        (field (name "MANUFACTURER PART NUMBER") "RC2512FK-0730RL")
        (field (name "MANUFACTURER") "YAGEO")
        (field (name "TOLERANCE") "1%")
      )
      (libsource (lib "database") (part "__template_resistor"))
    )
    (comp (ref "R24")
      (value "30")
      (footprint "R2512")
      (fields
        (field (name "MANUFACTURER PART NUMBER") "RC2512FK-0730RL")
        (field (name "MANUFACTURER") "YAGEO")
        (field (name "TOLERANCE") "1%")
      )
      (libsource (lib "database") (part "__template_resistor"))
    )
    (comp (ref "R25")
      (value "100")
      (footprint "R0402")
      (fields
        (field (name "MANUFACTURER PART NUMBER") "RC0402FR-07100RL")
        (field (name "MANUFACTURER") "YAGEO")
        (field (name "TOLERANCE") "1%")
      )
      (libsource (lib "database") (part "__template_resistor"))
    )
    (comp (ref "R26")
      (value "1k")
      (footprint "R0402")
      (fields
        (field (name "TOLERANCE") "1%")
        (field (name "MANUFACTURER PART NUMBER") "0402WGF1001TCE")
        (field (name "MANUFACTURER") "UNI-ROYAL(Uniroyal Elec)")
      )
      (libsource (lib "database") (part "__template_resistor"))
    )
    (comp (ref "R27")
      (value "30")
      (footprint "R2512")
      (fields
        (field (name "MANUFACTURER PART NUMBER") "RC2512FK-0730RL")
        (field (name "MANUFACTURER") "YAGEO")
        (field (name "TOLERANCE") "1%")
      )
      (libsource (lib "database") (part "__template_resistor"))
    )
    (comp (ref "R28")
      (value "30")
      (footprint "R2512")
      (fields
        (field (name "MANUFACTURER PART NUMBER") "RC2512FK-0730RL")
        (field (name "MANUFACTURER") "YAGEO")
        (field (name "TOLERANCE") "1%")
      )
      (libsource (lib "database") (part "__template_resistor"))
    )
    (comp (ref "R29")
      (value "100")
      (footprint "R0402")
      (fields
        (field (name "MANUFACTURER PART NUMBER") "RC0402FR-07100RL")
        (field (name "MANUFACTURER") "YAGEO")
        (field (name "TOLERANCE") "1%")
      )
      (libsource (lib "database") (part "__template_resistor"))
    )
    (comp (ref "R30")
      (value "1k")
      (footprint "R0402")
      (fields
        (field (name "TOLERANCE") "1%")
        (field (name "MANUFACTURER PART NUMBER") "0402WGF1001TCE")
        (field (name "MANUFACTURER") "UNI-ROYAL(Uniroyal Elec)")
      )
      (libsource (lib "database") (part "__template_resistor"))
    )
    (comp (ref "R31")
      (value "30")
      (footprint "R2512")
      (fields
        (field (name "MANUFACTURER PART NUMBER") "RC2512FK-0730RL")
        (field (name "MANUFACTURER") "YAGEO")
        (field (name "TOLERANCE") "1%")
      )
      (libsource (lib "database") (part "__template_resistor"))
    )
    (comp (ref "R32")
      (value "30")
      (footprint "R2512")
      (fields
        (field (name "MANUFACTURER PART NUMBER") "RC2512FK-0730RL")
        (field (name "MANUFACTURER") "YAGEO")
        (field (name "TOLERANCE") "1%")
      )
      (libsource (lib "database") (part "__template_resistor"))
    )
    (comp (ref "R33")
      (value "100")
      (footprint "R0402")
      (fields
        (field (name "MANUFACTURER PART NUMBER") "RC0402FR-07100RL")
        (field (name "MANUFACTURER") "YAGEO")
        (field (name "TOLERANCE") "1%")
      )
      (libsource (lib "database") (part "__template_resistor"))
    )
    (comp (ref "R34")
      (value "1k")
      (footprint "R0402")
      (fields
        (field (name "TOLERANCE") "1%")
        (field (name "MANUFACTURER PART NUMBER") "0402WGF1001TCE")
        (field (name "MANUFACTURER") "UNI-ROYAL(Uniroyal Elec)")
      )
      (libsource (lib "database") (part "__template_resistor"))
    )
    (comp (ref "R35")
      (value "10k")
      (footprint "R0402")
      (fields
        (field (name "TOLERANCE") "1%")
        (field (name "MANUFACTURER PART NUMBER") "0402WGF1002TCE")
        (field (name "MANUFACTURER") "UNI-ROYAL(Uniroyal Elec)")
      )
      (libsource (lib "database") (part "__template_resistor"))
    )
    (comp (ref "R36")
      (value "10k")
      (footprint "R0402")
      (fields
        (field (name "TOLERANCE") "1%")
        (field (name "MANUFACTURER PART NUMBER") "0402WGF1002TCE")
        (field (name "MANUFACTURER") "UNI-ROYAL(Uniroyal Elec)")
      )
      (libsource (lib "database") (part "__template_resistor"))
    )
    (comp (ref "R37")
      (value "10k")
      (footprint "R0402")
      (fields
        (field (name "TOLERANCE") "1%")
        (field (name "MANUFACTURER PART NUMBER") "0402WGF1002TCE")
        (field (name "MANUFACTURER") "UNI-ROYAL(Uniroyal Elec)")
      )
      (libsource (lib "database") (part "__template_resistor"))
    )
    (comp (ref "R38")
      (value "10k")
      (footprint "R0402")
      (fields
        (field (name "TOLERANCE") "1%")
        (field (name "MANUFACTURER PART NUMBER") "0402WGF1002TCE")
        (field (name "MANUFACTURER") "UNI-ROYAL(Uniroyal Elec)")
      )
      (libsource (lib "database") (part "__template_resistor"))
    )
    (comp (ref "R39")
      (value "30")
      (footprint "R2512")
      (fields
        (field (name "MANUFACTURER PART NUMBER") "RC2512FK-0730RL")
        (field (name "MANUFACTURER") "YAGEO")
        (field (name "TOLERANCE") "1%")
      )
      (libsource (lib "database") (part "__template_resistor"))
    )
    (comp (ref "R40")
      (value "10k")
      (footprint "R0402")
      (fields
        (field (name "TOLERANCE") "1%")
        (field (name "MANUFACTURER PART NUMBER") "0402WGF1002TCE")
        (field (name "MANUFACTURER") "UNI-ROYAL(Uniroyal Elec)")
      )
      (libsource (lib "database") (part "__template_resistor"))
    )
    (comp (ref "R41")
      (value "10k")
      (footprint "R0402")
      (fields
        (field (name "TOLERANCE") "1%")
        (field (name "MANUFACTURER PART NUMBER") "0402WGF1002TCE")
        (field (name "MANUFACTURER") "UNI-ROYAL(Uniroyal Elec)")
      )
      (libsource (lib "database") (part "__template_resistor"))
    )
    (comp (ref "R42")
      (value "10k")
      (footprint "R0402")
      (fields
        (field (name "TOLERANCE") "1%")
        (field (name "MANUFACTURER PART NUMBER") "0402WGF1002TCE")
        (field (name "MANUFACTURER") "UNI-ROYAL(Uniroyal Elec)")
      )
      (libsource (lib "database") (part "__template_resistor"))
    )
    (comp (ref "R43")
      (value "10k")
      (footprint "R0402")
      (fields
        (field (name "TOLERANCE") "1%")
        (field (name "MANUFACTURER PART NUMBER") "0402WGF1002TCE")
        (field (name "MANUFACTURER") "UNI-ROYAL(Uniroyal Elec)")
      )
      (libsource (lib "database") (part "__template_resistor"))
    )
    (comp (ref "R44")
      (value "30")
      (footprint "R2512")
      (fields
        (field (name "MANUFACTURER PART NUMBER") "RC2512FK-0730RL")
        (field (name "MANUFACTURER") "YAGEO")
        (field (name "TOLERANCE") "1%")
      )
      (libsource (lib "database") (part "__template_resistor"))
    )
    (comp (ref "R45")
      (value "100")
      (footprint "R0402")
      (fields
        (field (name "MANUFACTURER PART NUMBER") "RC0402FR-07100RL")
        (field (name "MANUFACTURER") "YAGEO")
        (field (name "TOLERANCE") "1%")
      )
      (libsource (lib "database") (part "__template_resistor"))
    )
    (comp (ref "R46")
      (value "1k")
      (footprint "R0402")
      (fields
        (field (name "TOLERANCE") "1%")
        (field (name "MANUFACTURER PART NUMBER") "0402WGF1001TCE")
        (field (name "MANUFACTURER") "UNI-ROYAL(Uniroyal Elec)")
      )
      (libsource (lib "database") (part "__template_resistor"))
    )
    (comp (ref "R47")
      (value "30")
      (footprint "R2512")
      (fields
        (field (name "MANUFACTURER PART NUMBER") "RC2512FK-0730RL")
        (field (name "MANUFACTURER") "YAGEO")
        (field (name "TOLERANCE") "1%")
      )
      (libsource (lib "database") (part "__template_resistor"))
    )
    (comp (ref "R48")
      (value "30")
      (footprint "R2512")
      (fields
        (field (name "MANUFACTURER PART NUMBER") "RC2512FK-0730RL")
        (field (name "MANUFACTURER") "YAGEO")
        (field (name "TOLERANCE") "1%")
      )
      (libsource (lib "database") (part "__template_resistor"))
    )
    (comp (ref "R49")
      (value "100")
      (footprint "R0402")
      (fields
        (field (name "MANUFACTURER PART NUMBER") "RC0402FR-07100RL")
        (field (name "MANUFACTURER") "YAGEO")
        (field (name "TOLERANCE") "1%")
      )
      (libsource (lib "database") (part "__template_resistor"))
    )
    (comp (ref "R50")
      (value "1k")
      (footprint "R0402")
      (fields
        (field (name "TOLERANCE") "1%")
        (field (name "MANUFACTURER PART NUMBER") "0402WGF1001TCE")
        (field (name "MANUFACTURER") "UNI-ROYAL(Uniroyal Elec)")
      )
      (libsource (lib "database") (part "__template_resistor"))
    )
    (comp (ref "R51")
      (value "30")
      (footprint "R2512")
      (fields
        (field (name "MANUFACTURER PART NUMBER") "RC2512FK-0730RL")
        (field (name "MANUFACTURER") "YAGEO")
        (field (name "TOLERANCE") "1%")
      )
      (libsource (lib "database") (part "__template_resistor"))
    )
    (comp (ref "R52")
      (value "30")
      (footprint "R2512")
      (fields
        (field (name "MANUFACTURER PART NUMBER") "RC2512FK-0730RL")
        (field (name "MANUFACTURER") "YAGEO")
        (field (name "TOLERANCE") "1%")
      )
      (libsource (lib "database") (part "__template_resistor"))
    )
    (comp (ref "R53")
      (value "100")
      (footprint "R0402")
      (fields
        (field (name "MANUFACTURER PART NUMBER") "RC0402FR-07100RL")
        (field (name "MANUFACTURER") "YAGEO")
        (field (name "TOLERANCE") "1%")
      )
      (libsource (lib "database") (part "__template_resistor"))
    )
    (comp (ref "R54")
      (value "1k")
      (footprint "R0402")
      (fields
        (field (name "TOLERANCE") "1%")
        (field (name "MANUFACTURER PART NUMBER") "0402WGF1001TCE")
        (field (name "MANUFACTURER") "UNI-ROYAL(Uniroyal Elec)")
      )
      (libsource (lib "database") (part "__template_resistor"))
    )
    (comp (ref "R55")
      (value "30")
      (footprint "R2512")
      (fields
        (field (name "MANUFACTURER PART NUMBER") "RC2512FK-0730RL")
        (field (name "MANUFACTURER") "YAGEO")
        (field (name "TOLERANCE") "1%")
      )
      (libsource (lib "database") (part "__template_resistor"))
    )
    (comp (ref "R56")
      (value "30")
      (footprint "R2512")
      (fields
        (field (name "MANUFACTURER PART NUMBER") "RC2512FK-0730RL")
        (field (name "MANUFACTURER") "YAGEO")
        (field (name "TOLERANCE") "1%")
      )
      (libsource (lib "database") (part "__template_resistor"))
    )
    (comp (ref "R57")
      (value "100")
      (footprint "R0402")
      (fields
        (field (name "MANUFACTURER PART NUMBER") "RC0402FR-07100RL")
        (field (name "MANUFACTURER") "YAGEO")
        (field (name "TOLERANCE") "1%")
      )
      (libsource (lib "database") (part "__template_resistor"))
    )
    (comp (ref "R58")
      (value "1k")
      (footprint "R0402")
      (fields
        (field (name "TOLERANCE") "1%")
        (field (name "MANUFACTURER PART NUMBER") "0402WGF1001TCE")
        (field (name "MANUFACTURER") "UNI-ROYAL(Uniroyal Elec)")
      )
      (libsource (lib "database") (part "__template_resistor"))
    )
    (comp (ref "R59")
      (value "30")
      (footprint "R2512")
      (fields
        (field (name "MANUFACTURER PART NUMBER") "RC2512FK-0730RL")
        (field (name "MANUFACTURER") "YAGEO")
        (field (name "TOLERANCE") "1%")
      )
      (libsource (lib "database") (part "__template_resistor"))
    )
    (comp (ref "R60")
      (value "30")
      (footprint "R2512")
      (fields
        (field (name "MANUFACTURER PART NUMBER") "RC2512FK-0730RL")
        (field (name "MANUFACTURER") "YAGEO")
        (field (name "TOLERANCE") "1%")
      )
      (libsource (lib "database") (part "__template_resistor"))
    )
    (comp (ref "R61")
      (value "100")
      (footprint "R0402")
      (fields
        (field (name "MANUFACTURER PART NUMBER") "RC0402FR-07100RL")
        (field (name "MANUFACTURER") "YAGEO")
        (field (name "TOLERANCE") "1%")
      )
      (libsource (lib "database") (part "__template_resistor"))
    )
    (comp (ref "R62")
      (value "1k")
      (footprint "R0402")
      (fields
        (field (name "TOLERANCE") "1%")
        (field (name "MANUFACTURER PART NUMBER") "0402WGF1001TCE")
        (field (name "MANUFACTURER") "UNI-ROYAL(Uniroyal Elec)")
      )
      (libsource (lib "database") (part "__template_resistor"))
    )
    (comp (ref "R63")
      (value "100")
      (footprint "R0402")
      (fields
        (field (name "MANUFACTURER PART NUMBER") "RC0402FR-07100RL")
        (field (name "MANUFACTURER") "YAGEO")
        (field (name "TOLERANCE") "1%")
      )
      (libsource (lib "database") (part "__template_resistor"))
    )
    (comp (ref "R64")
      (value "100")
      (footprint "R0402")
      (fields
        (field (name "MANUFACTURER PART NUMBER") "RC0402FR-07100RL")
        (field (name "MANUFACTURER") "YAGEO")
        (field (name "TOLERANCE") "1%")
      )
      (libsource (lib "database") (part "__template_resistor"))
    )
    (comp (ref "R65")
      (value "100")
      (footprint "R0402")
      (fields
        (field (name "MANUFACTURER PART NUMBER") "RC0402FR-07100RL")
        (field (name "MANUFACTURER") "YAGEO")
        (field (name "TOLERANCE") "1%")
      )
      (libsource (lib "database") (part "__template_resistor"))
    )
    (comp (ref "R66")
      (value "30")
      (footprint "R2512")
      (fields
        (field (name "MANUFACTURER PART NUMBER") "RC2512FK-0730RL")
        (field (name "MANUFACTURER") "YAGEO")
        (field (name "TOLERANCE") "1%")
      )
      (libsource (lib "database") (part "__template_resistor"))
    )
    (comp (ref "R67")
      (value "30")
      (footprint "R0402")
      (fields
        (field (name "MANUFACTURER PART NUMBER") "RC0402FR-0730RL")
        (field (name "MANUFACTURER") "YAGEO")
        (field (name "TOLERANCE") "1%")
      )
      (libsource (lib "database") (part "__template_resistor"))
    )
    (comp (ref "R68")
      (value "30")
      (footprint "R2512")
      (fields
        (field (name "MANUFACTURER PART NUMBER") "RC2512FK-0730RL")
        (field (name "MANUFACTURER") "YAGEO")
        (field (name "TOLERANCE") "1%")
      )
      (libsource (lib "database") (part "__template_resistor"))
    )
    (comp (ref "R69")
      (value "100")
      (footprint "R0402")
      (fields
        (field (name "MANUFACTURER PART NUMBER") "RC0402FR-07100RL")
        (field (name "MANUFACTURER") "YAGEO")
        (field (name "TOLERANCE") "1%")
      )
      (libsource (lib "database") (part "__template_resistor"))
    )
    (comp (ref "R70")
      (value "1k")
      (footprint "R0402")
      (fields
        (field (name "TOLERANCE") "1%")
        (field (name "MANUFACTURER PART NUMBER") "0402WGF1001TCE")
        (field (name "MANUFACTURER") "UNI-ROYAL(Uniroyal Elec)")
      )
      (libsource (lib "database") (part "__template_resistor"))
    )
    (comp (ref "R71")
      (value "30")
      (footprint "R2512")
      (fields
        (field (name "MANUFACTURER PART NUMBER") "RC2512FK-0730RL")
        (field (name "MANUFACTURER") "YAGEO")
        (field (name "TOLERANCE") "1%")
      )
      (libsource (lib "database") (part "__template_resistor"))
    )
    (comp (ref "R72")
      (value "30")
      (footprint "R2512")
      (fields
        (field (name "MANUFACTURER PART NUMBER") "RC2512FK-0730RL")
        (field (name "MANUFACTURER") "YAGEO")
        (field (name "TOLERANCE") "1%")
      )
      (libsource (lib "database") (part "__template_resistor"))
    )
    (comp (ref "R73")
      (value "100")
      (footprint "R0402")
      (fields
        (field (name "MANUFACTURER PART NUMBER") "RC0402FR-07100RL")
        (field (name "MANUFACTURER") "YAGEO")
        (field (name "TOLERANCE") "1%")
      )
      (libsource (lib "database") (part "__template_resistor"))
    )
    (comp (ref "R74")
      (value "1k")
      (footprint "R0402")
      (fields
        (field (name "TOLERANCE") "1%")
        (field (name "MANUFACTURER PART NUMBER") "0402WGF1001TCE")
        (field (name "MANUFACTURER") "UNI-ROYAL(Uniroyal Elec)")
      )
      (libsource (lib "database") (part "__template_resistor"))
    )
    (comp (ref "R75")
      (value "30")
      (footprint "R2512")
      (fields
        (field (name "MANUFACTURER PART NUMBER") "RC2512FK-0730RL")
        (field (name "MANUFACTURER") "YAGEO")
        (field (name "TOLERANCE") "1%")
      )
      (libsource (lib "database") (part "__template_resistor"))
    )
    (comp (ref "R76")
      (value "30")
      (footprint "R2512")
      (fields
        (field (name "MANUFACTURER PART NUMBER") "RC2512FK-0730RL")
        (field (name "MANUFACTURER") "YAGEO")
        (field (name "TOLERANCE") "1%")
      )
      (libsource (lib "database") (part "__template_resistor"))
    )
    (comp (ref "R77")
      (value "100")
      (footprint "R0402")
      (fields
        (field (name "MANUFACTURER PART NUMBER") "RC0402FR-07100RL")
        (field (name "MANUFACTURER") "YAGEO")
        (field (name "TOLERANCE") "1%")
      )
      (libsource (lib "database") (part "__template_resistor"))
    )
    (comp (ref "R78")
      (value "30")
      (footprint "R2512")
      (fields
        (field (name "MANUFACTURER PART NUMBER") "RC2512FK-0730RL")
        (field (name "MANUFACTURER") "YAGEO")
        (field (name "TOLERANCE") "1%")
      )
      (libsource (lib "database") (part "__template_resistor"))
    )
    (comp (ref "R79")
      (value "30")
      (footprint "R2512")
      (fields
        (field (name "MANUFACTURER PART NUMBER") "RC2512FK-0730RL")
        (field (name "MANUFACTURER") "YAGEO")
        (field (name "TOLERANCE") "1%")
      )
      (libsource (lib "database") (part "__template_resistor"))
    )
    (comp (ref "U1")
      (value "BQ79616PAPRQ1")
      (footprint "TI_PAP0064F")
      (description "IC MONITOR BATT STACK")
      (fields (field (name "MANUFACTURER") "Texas Instruments"))
      (libsource (lib "SSCP") (part "MONITOR_BQ79616PAPRQ1"))
    )
  )
  (nets
    (net (code "3") (name "/AVDD") (class "Default")
      (node (ref "C40") (pin "1") (pintype "passive"))
      (node (ref "U1") (pin "38") (pinfunction "AVDD_38") (pintype "passive"))
    )
    (net (code "4") (name "/BAT") (class "Default")
      (node (ref "C29") (pin "2") (pintype "passive"))
      (node (ref "C32") (pin "1") (pintype "passive"))
      (node (ref "R67") (pin "2") (pintype "passive"))
      (node (ref "U1") (pin "1") (pinfunction "BAT_1") (pintype "passive"))
    )
    (net (code "5") (name "/CB0") (class "Default")
      (node (ref "C38") (pin "2") (pintype "passive"))
      (node (ref "C44") (pin "1") (pintype "passive"))
      (node (ref "R78") (pin "1") (pintype "passive"))
      (node (ref "R79") (pin "2") (pintype "passive"))
      (node (ref "U1") (pin "34") (pinfunction "CB0_34") (pintype "passive"))
    )
    (net (code "6") (name "/CB1") (class "Default")
      (node (ref "C35") (pin "2") (pintype "passive"))
      (node (ref "C38") (pin "1") (pintype "passive"))
      (node (ref "D16") (pin "1") (pintype "passive"))
      (node (ref "R75") (pin "1") (pintype "passive"))
      (node (ref "R76") (pin "2") (pintype "passive"))
      (node (ref "U1") (pin "32") (pinfunction "CB1_32") (pintype "passive"))
    )
    (net (code "7") (name "/CB2") (class "Default")
      (node (ref "C30") (pin "2") (pintype "passive"))
      (node (ref "C35") (pin "1") (pintype "passive"))
      (node (ref "D15") (pin "1") (pintype "passive"))
      (node (ref "R71") (pin "1") (pintype "passive"))
      (node (ref "R72") (pin "2") (pintype "passive"))
      (node (ref "U1") (pin "30") (pinfunction "CB2_30") (pintype "passive"))
    )
    (net (code "8") (name "/CB3") (class "Default")
      (node (ref "C27") (pin "2") (pintype "passive"))
      (node (ref "C30") (pin "1") (pintype "passive"))
      (node (ref "D14") (pin "1") (pintype "passive"))
      (node (ref "R66") (pin "1") (pintype "passive"))
      (node (ref "R68") (pin "2") (pintype "passive"))
      (node (ref "U1") (pin "28") (pinfunction "CB3_28") (pintype "passive"))
    )
    (net (code "9") (name "/CB4") (class "Default")
      (node (ref "C25") (pin "2") (pintype "passive"))
      (node (ref "C27") (pin "1") (pintype "passive"))
      (node (ref "D13") (pin "1") (pintype "passive"))
      (node (ref "R59") (pin "1") (pintype "passive"))
      (node (ref "R60") (pin "2") (pintype "passive"))
      (node (ref "U1") (pin "26") (pinfunction "CB4_26") (pintype "passive"))
    )
    (net (code "10") (name "/CB5") (class "Default")
      (node (ref "C23") (pin "2") (pintype "passive"))
      (node (ref "C25") (pin "1") (pintype "passive"))
      (node (ref "D12") (pin "1") (pintype "passive"))
      (node (ref "R55") (pin "1") (pintype "passive"))
      (node (ref "R56") (pin "2") (pintype "passive"))
      (node (ref "U1") (pin "24") (pinfunction "CB5_24") (pintype "passive"))
    )
    (net (code "11") (name "/CB6") (class "Default")
      (node (ref "C21") (pin "2") (pintype "passive"))
      (node (ref "C23") (pin "1") (pintype "passive"))
      (node (ref "D11") (pin "1") (pintype "passive"))
      (node (ref "R51") (pin "1") (pintype "passive"))
      (node (ref "R52") (pin "2") (pintype "passive"))
      (node (ref "U1") (pin "22") (pinfunction "CB6_22") (pintype "passive"))
    )
    (net (code "12") (name "/CB7") (class "Default")
      (node (ref "C19") (pin "2") (pintype "passive"))
      (node (ref "C21") (pin "1") (pintype "passive"))
      (node (ref "D10") (pin "1") (pintype "passive"))
      (node (ref "R47") (pin "1") (pintype "passive"))
      (node (ref "R48") (pin "2") (pintype "passive"))
      (node (ref "U1") (pin "20") (pinfunction "CB7_20") (pintype "passive"))
    )
    (net (code "13") (name "/CB8") (class "Default")
      (node (ref "C16") (pin "2") (pintype "passive"))
      (node (ref "C19") (pin "1") (pintype "passive"))
      (node (ref "D9") (pin "1") (pintype "passive"))
      (node (ref "R39") (pin "1") (pintype "passive"))
      (node (ref "R44") (pin "2") (pintype "passive"))
      (node (ref "U1") (pin "18") (pinfunction "CB8_18") (pintype "passive"))
    )
    (net (code "14") (name "/CB9") (class "Default")
      (node (ref "C14") (pin "2") (pintype "passive"))
      (node (ref "C16") (pin "1") (pintype "passive"))
      (node (ref "D8") (pin "1") (pintype "passive"))
      (node (ref "R31") (pin "1") (pintype "passive"))
      (node (ref "R32") (pin "2") (pintype "passive"))
      (node (ref "U1") (pin "16") (pinfunction "CB9_16") (pintype "passive"))
    )
    (net (code "15") (name "/CB10") (class "Default")
      (node (ref "C12") (pin "2") (pintype "passive"))
      (node (ref "C14") (pin "1") (pintype "passive"))
      (node (ref "D7") (pin "1") (pintype "passive"))
      (node (ref "R27") (pin "1") (pintype "passive"))
      (node (ref "R28") (pin "2") (pintype "passive"))
      (node (ref "U1") (pin "14") (pinfunction "CB10_14") (pintype "passive"))
    )
    (net (code "16") (name "/CB11") (class "Default")
      (node (ref "C10") (pin "2") (pintype "passive"))
      (node (ref "C12") (pin "1") (pintype "passive"))
      (node (ref "D6") (pin "1") (pintype "passive"))
      (node (ref "R23") (pin "1") (pintype "passive"))
      (node (ref "R24") (pin "2") (pintype "passive"))
      (node (ref "U1") (pin "12") (pinfunction "CB11_12") (pintype "passive"))
    )
    (net (code "17") (name "/CB12") (class "Default")
      (node (ref "C10") (pin "1") (pintype "passive"))
      (node (ref "C8") (pin "2") (pintype "passive"))
      (node (ref "D5") (pin "1") (pintype "passive"))
      (node (ref "R19") (pin "1") (pintype "passive"))
      (node (ref "R20") (pin "2") (pintype "passive"))
      (node (ref "U1") (pin "10") (pinfunction "CB12_10") (pintype "passive"))
    )
    (net (code "18") (name "/CB13") (class "Default")
      (node (ref "C6") (pin "2") (pintype "passive"))
      (node (ref "C8") (pin "1") (pintype "passive"))
      (node (ref "D4") (pin "1") (pintype "passive"))
      (node (ref "R15") (pin "1") (pintype "passive"))
      (node (ref "R16") (pin "2") (pintype "passive"))
      (node (ref "U1") (pin "8") (pinfunction "CB13_8") (pintype "passive"))
    )
    (net (code "19") (name "/CB14") (class "Default")
      (node (ref "C4") (pin "2") (pintype "passive"))
      (node (ref "C6") (pin "1") (pintype "passive"))
      (node (ref "D3") (pin "1") (pintype "passive"))
      (node (ref "R11") (pin "1") (pintype "passive"))
      (node (ref "R12") (pin "2") (pintype "passive"))
      (node (ref "U1") (pin "6") (pinfunction "CB14_6") (pintype "passive"))
    )
    (net (code "20") (name "/CB15") (class "Default")
      (node (ref "C2") (pin "2") (pintype "passive"))
      (node (ref "C4") (pin "1") (pintype "passive"))
      (node (ref "D2") (pin "1") (pintype "passive"))
      (node (ref "R7") (pin "1") (pintype "passive"))
      (node (ref "R8") (pin "2") (pintype "passive"))
      (node (ref "U1") (pin "4") (pinfunction "CB15_4") (pintype "passive"))
    )
    (net (code "21") (name "/CB16") (class "Default")
      (node (ref "C2") (pin "1") (pintype "passive"))
      (node (ref "C29") (pin "1") (pintype "passive"))
      (node (ref "D1") (pin "1") (pintype "passive"))
      (node (ref "R3") (pin "1") (pintype "passive"))
      (node (ref "R4") (pin "2") (pintype "passive"))
      (node (ref "U1") (pin "2") (pinfunction "CB16_2") (pintype "passive"))
    )
    (net (code "22") (name "/CELL0") (class "Default")
      (node (ref "F18") (pin "1") (pintype "passive"))
      (node (ref "F19") (pin "1") (pintype "passive"))
      (node (ref "MH32") (pin "1") (pintype "passive"))
    )
    (net (code "23") (name "/CELL1") (class "Default")
      (node (ref "F17") (pin "1") (pintype "passive"))
      (node (ref "MH30") (pin "1") (pintype "passive"))
      (node (ref "MH31") (pin "1") (pintype "passive"))
    )
    (net (code "24") (name "/CELL2") (class "Default")
      (node (ref "F16") (pin "1") (pintype "passive"))
      (node (ref "MH28") (pin "1") (pintype "passive"))
      (node (ref "MH29") (pin "1") (pintype "passive"))
    )
    (net (code "25") (name "/CELL3") (class "Default")
      (node (ref "F15") (pin "1") (pintype "passive"))
      (node (ref "MH26") (pin "1") (pintype "passive"))
      (node (ref "MH27") (pin "1") (pintype "passive"))
    )
    (net (code "26") (name "/CELL4") (class "Default")
      (node (ref "F14") (pin "1") (pintype "passive"))
      (node (ref "MH24") (pin "1") (pintype "passive"))
      (node (ref "MH25") (pin "1") (pintype "passive"))
    )
    (net (code "27") (name "/CELL5") (class "Default")
      (node (ref "F13") (pin "1") (pintype "passive"))
      (node (ref "MH22") (pin "1") (pintype "passive"))
      (node (ref "MH23") (pin "1") (pintype "passive"))
    )
    (net (code "28") (name "/CELL6") (class "Default")
      (node (ref "F12") (pin "1") (pintype "passive"))
      (node (ref "MH20") (pin "1") (pintype "passive"))
      (node (ref "MH21") (pin "1") (pintype "passive"))
    )
    (net (code "29") (name "/CELL7") (class "Default")
      (node (ref "F11") (pin "1") (pintype "passive"))
      (node (ref "MH18") (pin "1") (pintype "passive"))
      (node (ref "MH19") (pin "1") (pintype "passive"))
    )
    (net (code "30") (name "/CELL8") (class "Default")
      (node (ref "F10") (pin "1") (pintype "passive"))
      (node (ref "MH16") (pin "1") (pintype "passive"))
      (node (ref "MH17") (pin "1") (pintype "passive"))
    )
    (net (code "31") (name "/CELL9") (class "Default")
      (node (ref "F9") (pin "1") (pintype "passive"))
      (node (ref "MH14") (pin "1") (pintype "passive"))
      (node (ref "MH15") (pin "1") (pintype "passive"))
    )
    (net (code "32") (name "/CELL10") (class "Default")
      (node (ref "F8") (pin "1") (pintype "passive"))
      (node (ref "MH12") (pin "1") (pintype "passive"))
      (node (ref "MH13") (pin "1") (pintype "passive"))
    )
    (net (code "33") (name "/CELL11") (class "Default")
      (node (ref "F7") (pin "1") (pintype "passive"))
      (node (ref "MH10") (pin "1") (pintype "passive"))
      (node (ref "MH11") (pin "1") (pintype "passive"))
    )
    (net (code "34") (name "/CELL12") (class "Default")
      (node (ref "F6") (pin "1") (pintype "passive"))
      (node (ref "MH8") (pin "1") (pintype "passive"))
      (node (ref "MH9") (pin "1") (pintype "passive"))
    )
    (net (code "35") (name "/CELL13") (class "Default")
      (node (ref "F5") (pin "1") (pintype "passive"))
      (node (ref "MH6") (pin "1") (pintype "passive"))
      (node (ref "MH7") (pin "1") (pintype "passive"))
    )
    (net (code "36") (name "/CELL14") (class "Default")
      (node (ref "F4") (pin "1") (pintype "passive"))
      (node (ref "MH4") (pin "1") (pintype "passive"))
      (node (ref "MH5") (pin "1") (pintype "passive"))
    )
    (net (code "37") (name "/CELL15") (class "Default")
      (node (ref "F3") (pin "1") (pintype "passive"))
      (node (ref "MH2") (pin "1") (pintype "passive"))
      (node (ref "MH3") (pin "1") (pintype "passive"))
    )
    (net (code "38") (name "/CELL16") (class "Default")
      (node (ref "F1") (pin "1") (pintype "passive"))
      (node (ref "F2") (pin "1") (pintype "passive"))
      (node (ref "MH1") (pin "1") (pintype "passive"))
    )
    (net (code "41") (name "/CVDD") (class "Default")
      (node (ref "C43") (pin "1") (pintype "passive"))
      (node (ref "U1") (pin "45") (pinfunction "CVDD_45") (pintype "passive"))
      (node (ref "U1") (pin "52") (pinfunction "RX_52") (pintype "passive"))
    )
    (net (code "42") (name "/DVDD") (class "Default")
      (node (ref "C39") (pin "1") (pintype "passive"))
      (node (ref "U1") (pin "49") (pinfunction "DVDD_49") (pintype "passive"))
    )
    (net (code "43") (name "/FUSED0") (class "Default")
      (node (ref "F18") (pin "2") (pintype "passive"))
      (node (ref "R77") (pin "1") (pintype "passive"))
      (node (ref "R78") (pin "2") (pintype "passive"))
      (node (ref "R79") (pin "1") (pintype "passive"))
    )
    (net (code "44") (name "/FUSED1") (class "Default")
      (node (ref "F17") (pin "2") (pintype "passive"))
      (node (ref "R73") (pin "1") (pintype "passive"))
      (node (ref "R74") (pin "1") (pintype "passive"))
      (node (ref "R75") (pin "2") (pintype "passive"))
      (node (ref "R76") (pin "1") (pintype "passive"))
    )
    (net (code "45") (name "/FUSED2") (class "Default")
      (node (ref "F16") (pin "2") (pintype "passive"))
      (node (ref "R69") (pin "1") (pintype "passive"))
      (node (ref "R70") (pin "1") (pintype "passive"))
      (node (ref "R71") (pin "2") (pintype "passive"))
      (node (ref "R72") (pin "1") (pintype "passive"))
    )
    (net (code "46") (name "/FUSED3") (class "Default")
      (node (ref "F15") (pin "2") (pintype "passive"))
      (node (ref "R61") (pin "1") (pintype "passive"))
      (node (ref "R62") (pin "1") (pintype "passive"))
      (node (ref "R66") (pin "2") (pintype "passive"))
      (node (ref "R68") (pin "1") (pintype "passive"))
    )
    (net (code "47") (name "/FUSED4") (class "Default")
      (node (ref "F14") (pin "2") (pintype "passive"))
      (node (ref "R57") (pin "1") (pintype "passive"))
      (node (ref "R58") (pin "1") (pintype "passive"))
      (node (ref "R59") (pin "2") (pintype "passive"))
      (node (ref "R60") (pin "1") (pintype "passive"))
    )
    (net (code "48") (name "/FUSED5") (class "Default")
      (node (ref "F13") (pin "2") (pintype "passive"))
      (node (ref "R53") (pin "1") (pintype "passive"))
      (node (ref "R54") (pin "1") (pintype "passive"))
      (node (ref "R55") (pin "2") (pintype "passive"))
      (node (ref "R56") (pin "1") (pintype "passive"))
    )
    (net (code "49") (name "/FUSED6") (class "Default")
      (node (ref "F12") (pin "2") (pintype "passive"))
      (node (ref "R49") (pin "1") (pintype "passive"))
      (node (ref "R50") (pin "1") (pintype "passive"))
      (node (ref "R51") (pin "2") (pintype "passive"))
      (node (ref "R52") (pin "1") (pintype "passive"))
    )
    (net (code "50") (name "/FUSED7") (class "Default")
      (node (ref "F11") (pin "2") (pintype "passive"))
      (node (ref "R45") (pin "1") (pintype "passive"))
      (node (ref "R46") (pin "1") (pintype "passive"))
      (node (ref "R47") (pin "2") (pintype "passive"))
      (node (ref "R48") (pin "1") (pintype "passive"))
    )
    (net (code "51") (name "/FUSED8") (class "Default")
      (node (ref "F10") (pin "2") (pintype "passive"))
      (node (ref "R33") (pin "1") (pintype "passive"))
      (node (ref "R34") (pin "1") (pintype "passive"))
      (node (ref "R39") (pin "2") (pintype "passive"))
      (node (ref "R44") (pin "1") (pintype "passive"))
    )
    (net (code "52") (name "/FUSED9") (class "Default")
      (node (ref "F9") (pin "2") (pintype "passive"))
      (node (ref "R29") (pin "1") (pintype "passive"))
      (node (ref "R30") (pin "1") (pintype "passive"))
      (node (ref "R31") (pin "2") (pintype "passive"))
      (node (ref "R32") (pin "1") (pintype "passive"))
    )
    (net (code "53") (name "/FUSED10") (class "Default")
      (node (ref "F8") (pin "2") (pintype "passive"))
      (node (ref "R25") (pin "1") (pintype "passive"))
      (node (ref "R26") (pin "1") (pintype "passive"))
      (node (ref "R27") (pin "2") (pintype "passive"))
      (node (ref "R28") (pin "1") (pintype "passive"))
    )
    (net (code "54") (name "/FUSED11") (class "Default")
      (node (ref "F7") (pin "2") (pintype "passive"))
      (node (ref "R21") (pin "1") (pintype "passive"))
      (node (ref "R22") (pin "1") (pintype "passive"))
      (node (ref "R23") (pin "2") (pintype "passive"))
      (node (ref "R24") (pin "1") (pintype "passive"))
    )
    (net (code "55") (name "/FUSED12") (class "Default")
      (node (ref "F6") (pin "2") (pintype "passive"))
      (node (ref "R17") (pin "1") (pintype "passive"))
      (node (ref "R18") (pin "1") (pintype "passive"))
      (node (ref "R19") (pin "2") (pintype "passive"))
      (node (ref "R20") (pin "1") (pintype "passive"))
    )
    (net (code "56") (name "/FUSED13") (class "Default")
      (node (ref "F5") (pin "2") (pintype "passive"))
      (node (ref "R13") (pin "1") (pintype "passive"))
      (node (ref "R14") (pin "1") (pintype "passive"))
      (node (ref "R15") (pin "2") (pintype "passive"))
      (node (ref "R16") (pin "1") (pintype "passive"))
    )
    (net (code "57") (name "/FUSED14") (class "Default")
      (node (ref "F4") (pin "2") (pintype "passive"))
      (node (ref "R10") (pin "1") (pintype "passive"))
      (node (ref "R11") (pin "2") (pintype "passive"))
      (node (ref "R12") (pin "1") (pintype "passive"))
      (node (ref "R9") (pin "1") (pintype "passive"))
    )
    (net (code "58") (name "/FUSED15") (class "Default")
      (node (ref "F3") (pin "2") (pintype "passive"))
      (node (ref "R5") (pin "1") (pintype "passive"))
      (node (ref "R6") (pin "1") (pintype "passive"))
      (node (ref "R7") (pin "2") (pintype "passive"))
      (node (ref "R8") (pin "1") (pintype "passive"))
    )
    (net (code "59") (name "/FUSED16") (class "Default")
      (node (ref "F2") (pin "2") (pintype "passive"))
      (node (ref "R1") (pin "1") (pintype "passive"))
      (node (ref "R2") (pin "1") (pintype "passive"))
      (node (ref "R3") (pin "2") (pintype "passive"))
      (node (ref "R4") (pin "1") (pintype "passive"))
    )
    (net (code "60") (name "/GPIO1") (class "Default")
      (node (ref "J1") (pin "3") (pintype "passive"))
      (node (ref "J1") (pin "4") (pintype "passive"))
      (node (ref "R35") (pin "2") (pintype "passive"))
      (node (ref "U1") (pin "61") (pinfunction "GPIO1_61") (pintype "passive"))
    )
    (net (code "61") (name "/GPIO2") (class "Default")
      (node (ref "J2") (pin "3") (pintype "passive"))
      (node (ref "J2") (pin "4") (pintype "passive"))
      (node (ref "R40") (pin "2") (pintype "passive"))
      (node (ref "U1") (pin "60") (pinfunction "GPIO2_60") (pintype "passive"))
    )
    (net (code "62") (name "/GPIO3") (class "Default")
      (node (ref "J3") (pin "3") (pintype "passive"))
      (node (ref "J3") (pin "4") (pintype "passive"))
      (node (ref "R36") (pin "2") (pintype "passive"))
      (node (ref "U1") (pin "59") (pinfunction "GPIO3_59") (pintype "passive"))
    )
    (net (code "63") (name "/GPIO4") (class "Default")
      (node (ref "J4") (pin "3") (pintype "passive"))
      (node (ref "J4") (pin "4") (pintype "passive"))
      (node (ref "R41") (pin "2") (pintype "passive"))
      (node (ref "U1") (pin "58") (pinfunction "GPIO4_58") (pintype "passive"))
    )
    (net (code "64") (name "/GPIO5") (class "Default")
      (node (ref "J5") (pin "3") (pintype "passive"))
      (node (ref "J5") (pin "4") (pintype "passive"))
      (node (ref "R37") (pin "2") (pintype "passive"))
      (node (ref "U1") (pin "57") (pinfunction "GPIO5_57") (pintype "passive"))
    )
    (net (code "65") (name "/GPIO6") (class "Default")
      (node (ref "J6") (pin "3") (pintype "passive"))
      (node (ref "J6") (pin "4") (pintype "passive"))
      (node (ref "R42") (pin "2") (pintype "passive"))
      (node (ref "U1") (pin "56") (pinfunction "GPIO6_56") (pintype "passive"))
    )
    (net (code "66") (name "/GPIO7") (class "Default")
      (node (ref "J7") (pin "3") (pintype "passive"))
      (node (ref "J7") (pin "4") (pintype "passive"))
      (node (ref "R38") (pin "2") (pintype "passive"))
      (node (ref "U1") (pin "55") (pinfunction "GPIO7_55") (pintype "passive"))
    )
    (net (code "67") (name "/GPIO8") (class "Default")
      (node (ref "J8") (pin "3") (pintype "passive"))
      (node (ref "J8") (pin "4") (pintype "passive"))
      (node (ref "R43") (pin "2") (pintype "passive"))
      (node (ref "U1") (pin "54") (pinfunction "GPIO8_54") (pintype "passive"))
    )
    (net (code "68") (name "/LDOIN") (class "Default")
      (node (ref "C34") (pin "1") (pintype "passive"))
      (node (ref "Q1") (pin "3") (pinfunction "E_3") (pintype "passive"))
      (node (ref "U1") (pin "47") (pinfunction "LDOIN_47") (pintype "passive"))
    )
    (net (code "69") (name "/NEG5V") (class "Default")
      (node (ref "C41") (pin "1") (pintype "passive"))
      (node (ref "U1") (pin "44") (pinfunction "NEG5V_44") (pintype "passive"))
    )
    (net (code "70") (name "/NPNB") (class "Default")
      (node (ref "Q1") (pin "1") (pinfunction "B_1") (pintype "passive"))
      (node (ref "U1") (pin "48") (pinfunction "NPNB_48") (pintype "passive"))
    )
    (net (code "71") (name "/NPNC") (class "Default")
      (node (ref "C31") (pin "1") (pintype "passive"))
      (node (ref "Q1") (pin "2") (pinfunction "C_2") (pintype "passive"))
      (node (ref "Q1") (pin "4") (pinfunction "C_4") (pintype "passive"))
      (node (ref "R65") (pin "1") (pintype "passive"))
    )
    (net (code "72") (name "/REFHP") (class "Default")
      (node (ref "C36") (pin "1") (pintype "passive"))
      (node (ref "U1") (pin "37") (pinfunction "REFHP_37") (pintype "passive"))
    )
    (net (code "73") (name "/TSREF") (class "Default")
      (node (ref "C18") (pin "1") (pintype "passive"))
      (node (ref "R35") (pin "1") (pintype "passive"))
      (node (ref "R36") (pin "1") (pintype "passive"))
      (node (ref "R37") (pin "1") (pintype "passive"))
      (node (ref "R38") (pin "1") (pintype "passive"))
      (node (ref "R40") (pin "1") (pintype "passive"))
      (node (ref "R41") (pin "1") (pintype "passive"))
      (node (ref "R42") (pin "1") (pintype "passive"))
      (node (ref "R43") (pin "1") (pintype "passive"))
      (node (ref "U1") (pin "51") (pinfunction "TSREF_51") (pintype "passive"))
    )
    (net (code "74") (name "/VC0") (class "Default")
      (node (ref "C37") (pin "2") (pintype "passive"))
      (node (ref "C42") (pin "1") (pintype "passive"))
      (node (ref "R77") (pin "2") (pintype "passive"))
      (node (ref "U1") (pin "35") (pinfunction "VC0_35") (pintype "passive"))
    )
    (net (code "75") (name "/VC1") (class "Default")
      (node (ref "C33") (pin "2") (pintype "passive"))
      (node (ref "C37") (pin "1") (pintype "passive"))
      (node (ref "R73") (pin "2") (pintype "passive"))
      (node (ref "U1") (pin "33") (pinfunction "VC1_33") (pintype "passive"))
    )
    (net (code "76") (name "/VC2") (class "Default")
      (node (ref "C28") (pin "2") (pintype "passive"))
      (node (ref "C33") (pin "1") (pintype "passive"))
      (node (ref "R69") (pin "2") (pintype "passive"))
      (node (ref "U1") (pin "31") (pinfunction "VC2_31") (pintype "passive"))
    )
    (net (code "77") (name "/VC3") (class "Default")
      (node (ref "C26") (pin "2") (pintype "passive"))
      (node (ref "C28") (pin "1") (pintype "passive"))
      (node (ref "R61") (pin "2") (pintype "passive"))
      (node (ref "U1") (pin "29") (pinfunction "VC3_29") (pintype "passive"))
    )
    (net (code "78") (name "/VC4") (class "Default")
      (node (ref "C24") (pin "2") (pintype "passive"))
      (node (ref "C26") (pin "1") (pintype "passive"))
      (node (ref "R57") (pin "2") (pintype "passive"))
      (node (ref "U1") (pin "27") (pinfunction "VC4_27") (pintype "passive"))
    )
    (net (code "79") (name "/VC5") (class "Default")
      (node (ref "C22") (pin "2") (pintype "passive"))
      (node (ref "C24") (pin "1") (pintype "passive"))
      (node (ref "R53") (pin "2") (pintype "passive"))
      (node (ref "U1") (pin "25") (pinfunction "VC5_25") (pintype "passive"))
    )
    (net (code "80") (name "/VC6") (class "Default")
      (node (ref "C20") (pin "2") (pintype "passive"))
      (node (ref "C22") (pin "1") (pintype "passive"))
      (node (ref "R49") (pin "2") (pintype "passive"))
      (node (ref "U1") (pin "23") (pinfunction "VC6_23") (pintype "passive"))
    )
    (net (code "81") (name "/VC7") (class "Default")
      (node (ref "C17") (pin "2") (pintype "passive"))
      (node (ref "C20") (pin "1") (pintype "passive"))
      (node (ref "R45") (pin "2") (pintype "passive"))
      (node (ref "U1") (pin "21") (pinfunction "VC7_21") (pintype "passive"))
    )
    (net (code "82") (name "/VC8") (class "Default")
      (node (ref "C15") (pin "2") (pintype "passive"))
      (node (ref "C17") (pin "1") (pintype "passive"))
      (node (ref "R33") (pin "2") (pintype "passive"))
      (node (ref "U1") (pin "19") (pinfunction "VC8_19") (pintype "passive"))
    )
    (net (code "83") (name "/VC9") (class "Default")
      (node (ref "C13") (pin "2") (pintype "passive"))
      (node (ref "C15") (pin "1") (pintype "passive"))
      (node (ref "R29") (pin "2") (pintype "passive"))
      (node (ref "U1") (pin "17") (pinfunction "VC9_17") (pintype "passive"))
    )
    (net (code "84") (name "/VC10") (class "Default")
      (node (ref "C11") (pin "2") (pintype "passive"))
      (node (ref "C13") (pin "1") (pintype "passive"))
      (node (ref "R25") (pin "2") (pintype "passive"))
      (node (ref "U1") (pin "15") (pinfunction "VC10_15") (pintype "passive"))
    )
    (net (code "85") (name "/VC11") (class "Default")
      (node (ref "C11") (pin "1") (pintype "passive"))
      (node (ref "C9") (pin "2") (pintype "passive"))
      (node (ref "R21") (pin "2") (pintype "passive"))
      (node (ref "U1") (pin "13") (pinfunction "VC11_13") (pintype "passive"))
    )
    (net (code "86") (name "/VC12") (class "Default")
      (node (ref "C7") (pin "2") (pintype "passive"))
      (node (ref "C9") (pin "1") (pintype "passive"))
      (node (ref "R17") (pin "2") (pintype "passive"))
      (node (ref "U1") (pin "11") (pinfunction "VC12_11") (pintype "passive"))
    )
    (net (code "87") (name "/VC13") (class "Default")
      (node (ref "C5") (pin "2") (pintype "passive"))
      (node (ref "C7") (pin "1") (pintype "passive"))
      (node (ref "R13") (pin "2") (pintype "passive"))
      (node (ref "U1") (pin "9") (pinfunction "VC13_9") (pintype "passive"))
    )
    (net (code "88") (name "/VC14") (class "Default")
      (node (ref "C3") (pin "2") (pintype "passive"))
      (node (ref "C5") (pin "1") (pintype "passive"))
      (node (ref "R9") (pin "2") (pintype "passive"))
      (node (ref "U1") (pin "7") (pinfunction "VC14_7") (pintype "passive"))
    )
    (net (code "89") (name "/VC15") (class "Default")
      (node (ref "C1") (pin "2") (pintype "passive"))
      (node (ref "C3") (pin "1") (pintype "passive"))
      (node (ref "R5") (pin "2") (pintype "passive"))
      (node (ref "U1") (pin "5") (pinfunction "VC15_5") (pintype "passive"))
    )
    (net (code "90") (name "/VC16") (class "Default")
      (node (ref "C1") (pin "1") (pintype "passive"))
      (node (ref "R1") (pin "2") (pintype "passive"))
      (node (ref "U1") (pin "3") (pinfunction "VC16_3") (pintype "passive"))
    )
    (net (code "91") (name "GND") (class "Default")
      (node (ref "C18") (pin "2") (pintype "passive"))
      (node (ref "C31") (pin "2") (pintype "passive"))
      (node (ref "C32") (pin "2") (pintype "passive"))
      (node (ref "C34") (pin "2") (pintype "passive"))
      (node (ref "C36") (pin "2") (pintype "passive"))
      (node (ref "C39") (pin "2") (pintype "passive"))
      (node (ref "C40") (pin "2") (pintype "passive"))
      (node (ref "C41") (pin "2") (pintype "passive"))
      (node (ref "C42") (pin "2") (pintype "passive"))
      (node (ref "C43") (pin "2") (pintype "passive"))
      (node (ref "C44") (pin "2") (pintype "passive"))
      (node (ref "F19") (pin "2") (pintype "passive"))
      (node (ref "J1") (pin "1") (pintype "passive"))
      (node (ref "J1") (pin "2") (pintype "passive"))
      (node (ref "J2") (pin "1") (pintype "passive"))
      (node (ref "J2") (pin "2") (pintype "passive"))
      (node (ref "J3") (pin "1") (pintype "passive"))
      (node (ref "J3") (pin "2") (pintype "passive"))
      (node (ref "J4") (pin "1") (pintype "passive"))
      (node (ref "J4") (pin "2") (pintype "passive"))
      (node (ref "J5") (pin "1") (pintype "passive"))
      (node (ref "J5") (pin "2") (pintype "passive"))
      (node (ref "J6") (pin "1") (pintype "passive"))
      (node (ref "J6") (pin "2") (pintype "passive"))
      (node (ref "J7") (pin "1") (pintype "passive"))
      (node (ref "J7") (pin "2") (pintype "passive"))
      (node (ref "J8") (pin "1") (pintype "passive"))
      (node (ref "J8") (pin "2") (pintype "passive"))
      (node (ref "U1") (pin "36") (pinfunction "REFHM_36") (pintype "passive"))
      (node (ref "U1") (pin "39") (pinfunction "AVSS_39") (pintype "passive"))
      (node (ref "U1") (pin "46") (pinfunction "CVSS_46") (pintype "passive"))
      (node (ref "U1") (pin "50") (pinfunction "DVSS_50") (pintype "passive"))
      (node (ref "U1") (pin "EP0") (pinfunction "PAD_EP0") (pintype "passive"))
    )
    (net (code "92") (name "Net-(D1-Pad2)") (class "Default")
      (node (ref "D1") (pin "2") (pintype "passive"))
      (node (ref "R2") (pin "2") (pintype "passive"))
    )
    (net (code "93") (name "Net-(D2-Pad2)") (class "Default")
      (node (ref "D2") (pin "2") (pintype "passive"))
      (node (ref "R6") (pin "2") (pintype "passive"))
    )
    (net (code "94") (name "Net-(D3-Pad2)") (class "Default")
      (node (ref "D3") (pin "2") (pintype "passive"))
      (node (ref "R10") (pin "2") (pintype "passive"))
    )
    (net (code "95") (name "Net-(D4-Pad2)") (class "Default")
      (node (ref "D4") (pin "2") (pintype "passive"))
      (node (ref "R14") (pin "2") (pintype "passive"))
    )
    (net (code "96") (name "Net-(D5-Pad2)") (class "Default")
      (node (ref "D5") (pin "2") (pintype "passive"))
      (node (ref "R18") (pin "2") (pintype "passive"))
    )
    (net (code "97") (name "Net-(D6-Pad2)") (class "Default")
      (node (ref "D6") (pin "2") (pintype "passive"))
      (node (ref "R22") (pin "2") (pintype "passive"))
    )
    (net (code "98") (name "Net-(D7-Pad2)") (class "Default")
      (node (ref "D7") (pin "2") (pintype "passive"))
      (node (ref "R26") (pin "2") (pintype "passive"))
    )
    (net (code "99") (name "Net-(D8-Pad2)") (class "Default")
      (node (ref "D8") (pin "2") (pintype "passive"))
      (node (ref "R30") (pin "2") (pintype "passive"))
    )
    (net (code "100") (name "Net-(D9-Pad2)") (class "Default")
      (node (ref "D9") (pin "2") (pintype "passive"))
      (node (ref "R34") (pin "2") (pintype "passive"))
    )
    (net (code "101") (name "Net-(D10-Pad2)") (class "Default")
      (node (ref "D10") (pin "2") (pintype "passive"))
      (node (ref "R46") (pin "2") (pintype "passive"))
    )
    (net (code "102") (name "Net-(D11-Pad2)") (class "Default")
      (node (ref "D11") (pin "2") (pintype "passive"))
      (node (ref "R50") (pin "2") (pintype "passive"))
    )
    (net (code "103") (name "Net-(D12-Pad2)") (class "Default")
      (node (ref "D12") (pin "2") (pintype "passive"))
      (node (ref "R54") (pin "2") (pintype "passive"))
    )
    (net (code "104") (name "Net-(D13-Pad2)") (class "Default")
      (node (ref "D13") (pin "2") (pintype "passive"))
      (node (ref "R58") (pin "2") (pintype "passive"))
    )
    (net (code "105") (name "Net-(D14-Pad2)") (class "Default")
      (node (ref "D14") (pin "2") (pintype "passive"))
      (node (ref "R62") (pin "2") (pintype "passive"))
    )
    (net (code "106") (name "Net-(D15-Pad2)") (class "Default")
      (node (ref "D15") (pin "2") (pintype "passive"))
      (node (ref "R70") (pin "2") (pintype "passive"))
    )
    (net (code "107") (name "Net-(D16-Pad2)") (class "Default")
      (node (ref "D16") (pin "2") (pintype "passive"))
      (node (ref "R74") (pin "2") (pintype "passive"))
    )
    (net (code "108") (name "Net-(F1-Pad2)") (class "Default")
      (node (ref "F1") (pin "2") (pintype "passive"))
      (node (ref "R63") (pin "2") (pintype "passive"))
      (node (ref "R67") (pin "1") (pintype "passive"))
    )
    (net (code "109") (name "Net-(R63-Pad1)") (class "Default")
      (node (ref "R63") (pin "1") (pintype "passive"))
      (node (ref "R64") (pin "2") (pintype "passive"))
    )
    (net (code "110") (name "Net-(R64-Pad1)") (class "Default")
      (node (ref "R64") (pin "1") (pintype "passive"))
      (node (ref "R65") (pin "2") (pintype "passive"))
    )
    (net (code "111") (name "unconnected-(J1-TAB-PadEP0)") (class "Default")
      (node (ref "J1") (pin "EP0") (pinfunction "TAB_EP0") (pintype "passive"))
    )
    (net (code "112") (name "unconnected-(J1-TAB-PadEP1)") (class "Default")
      (node (ref "J1") (pin "EP1") (pinfunction "TAB_EP1") (pintype "passive"))
    )
    (net (code "113") (name "unconnected-(J2-TAB-PadEP0)") (class "Default")
      (node (ref "J2") (pin "EP0") (pinfunction "TAB_EP0") (pintype "passive"))
    )
    (net (code "114") (name "unconnected-(J2-TAB-PadEP1)") (class "Default")
      (node (ref "J2") (pin "EP1") (pinfunction "TAB_EP1") (pintype "passive"))
    )
    (net (code "115") (name "unconnected-(J3-TAB-PadEP0)") (class "Default")
      (node (ref "J3") (pin "EP0") (pinfunction "TAB_EP0") (pintype "passive"))
    )
    (net (code "116") (name "unconnected-(J3-TAB-PadEP1)") (class "Default")
      (node (ref "J3") (pin "EP1") (pinfunction "TAB_EP1") (pintype "passive"))
    )
    (net (code "117") (name "unconnected-(J4-TAB-PadEP0)") (class "Default")
      (node (ref "J4") (pin "EP0") (pinfunction "TAB_EP0") (pintype "passive"))
    )
    (net (code "118") (name "unconnected-(J4-TAB-PadEP1)") (class "Default")
      (node (ref "J4") (pin "EP1") (pinfunction "TAB_EP1") (pintype "passive"))
    )
    (net (code "119") (name "unconnected-(J5-TAB-PadEP0)") (class "Default")
      (node (ref "J5") (pin "EP0") (pinfunction "TAB_EP0") (pintype "passive"))
    )
    (net (code "120") (name "unconnected-(J5-TAB-PadEP1)") (class "Default")
      (node (ref "J5") (pin "EP1") (pinfunction "TAB_EP1") (pintype "passive"))
    )
    (net (code "121") (name "unconnected-(J6-TAB-PadEP0)") (class "Default")
      (node (ref "J6") (pin "EP0") (pinfunction "TAB_EP0") (pintype "passive"))
    )
    (net (code "122") (name "unconnected-(J6-TAB-PadEP1)") (class "Default")
      (node (ref "J6") (pin "EP1") (pinfunction "TAB_EP1") (pintype "passive"))
    )
    (net (code "123") (name "unconnected-(J7-TAB-PadEP0)") (class "Default")
      (node (ref "J7") (pin "EP0") (pinfunction "TAB_EP0") (pintype "passive"))
    )
    (net (code "124") (name "unconnected-(J7-TAB-PadEP1)") (class "Default")
      (node (ref "J7") (pin "EP1") (pinfunction "TAB_EP1") (pintype "passive"))
    )
    (net (code "125") (name "unconnected-(J8-TAB-PadEP0)") (class "Default")
      (node (ref "J8") (pin "EP0") (pinfunction "TAB_EP0") (pintype "passive"))
    )
    (net (code "126") (name "unconnected-(J8-TAB-PadEP1)") (class "Default")
      (node (ref "J8") (pin "EP1") (pinfunction "TAB_EP1") (pintype "passive"))
    )
    (net (code "127") (name "unconnected-(U1B-BBN-Pad63)") (class "Default")
      (node (ref "U1") (pin "63") (pinfunction "BBN_63") (pintype "passive"))
    )
    (net (code "128") (name "unconnected-(U1B-BBP-Pad64)") (class "Default")
      (node (ref "U1") (pin "64") (pinfunction "BBP_64") (pintype "passive"))
    )
    (net (code "129") (name "unconnected-(U1B-nFAULT-Pad62)") (class "Default")
      (node (ref "U1") (pin "62") (pinfunction "nFAULT_62") (pintype "passive"))
    )
    (net (code "130") (name "unconnected-(U1C-COMHN-Pad42)") (class "Default")
      (node (ref "U1") (pin "42") (pinfunction "COMHN_42") (pintype "passive"))
    )
    (net (code "131") (name "unconnected-(U1C-COMHP-Pad43)") (class "Default")
      (node (ref "U1") (pin "43") (pinfunction "COMHP_43") (pintype "passive"))
    )
    (net (code "132") (name "unconnected-(U1C-COMLN-Pad41)") (class "Default")
      (node (ref "U1") (pin "41") (pinfunction "COMLN_41") (pintype "passive"))
    )
    (net (code "133") (name "unconnected-(U1C-COMLP-Pad40)") (class "Default")
      (node (ref "U1") (pin "40") (pinfunction "COMLP_40") (pintype "passive"))
    )
    (net (code "134") (name "unconnected-(U1C-TX-Pad53)") (class "Default")
      (node (ref "U1") (pin "53") (pinfunction "TX_53") (pintype "passive"))
    )
  )
)
